# EEZ_DIB_DCM220_r2B7.net
KiCad netlist of a schematic drawn in EAGLE
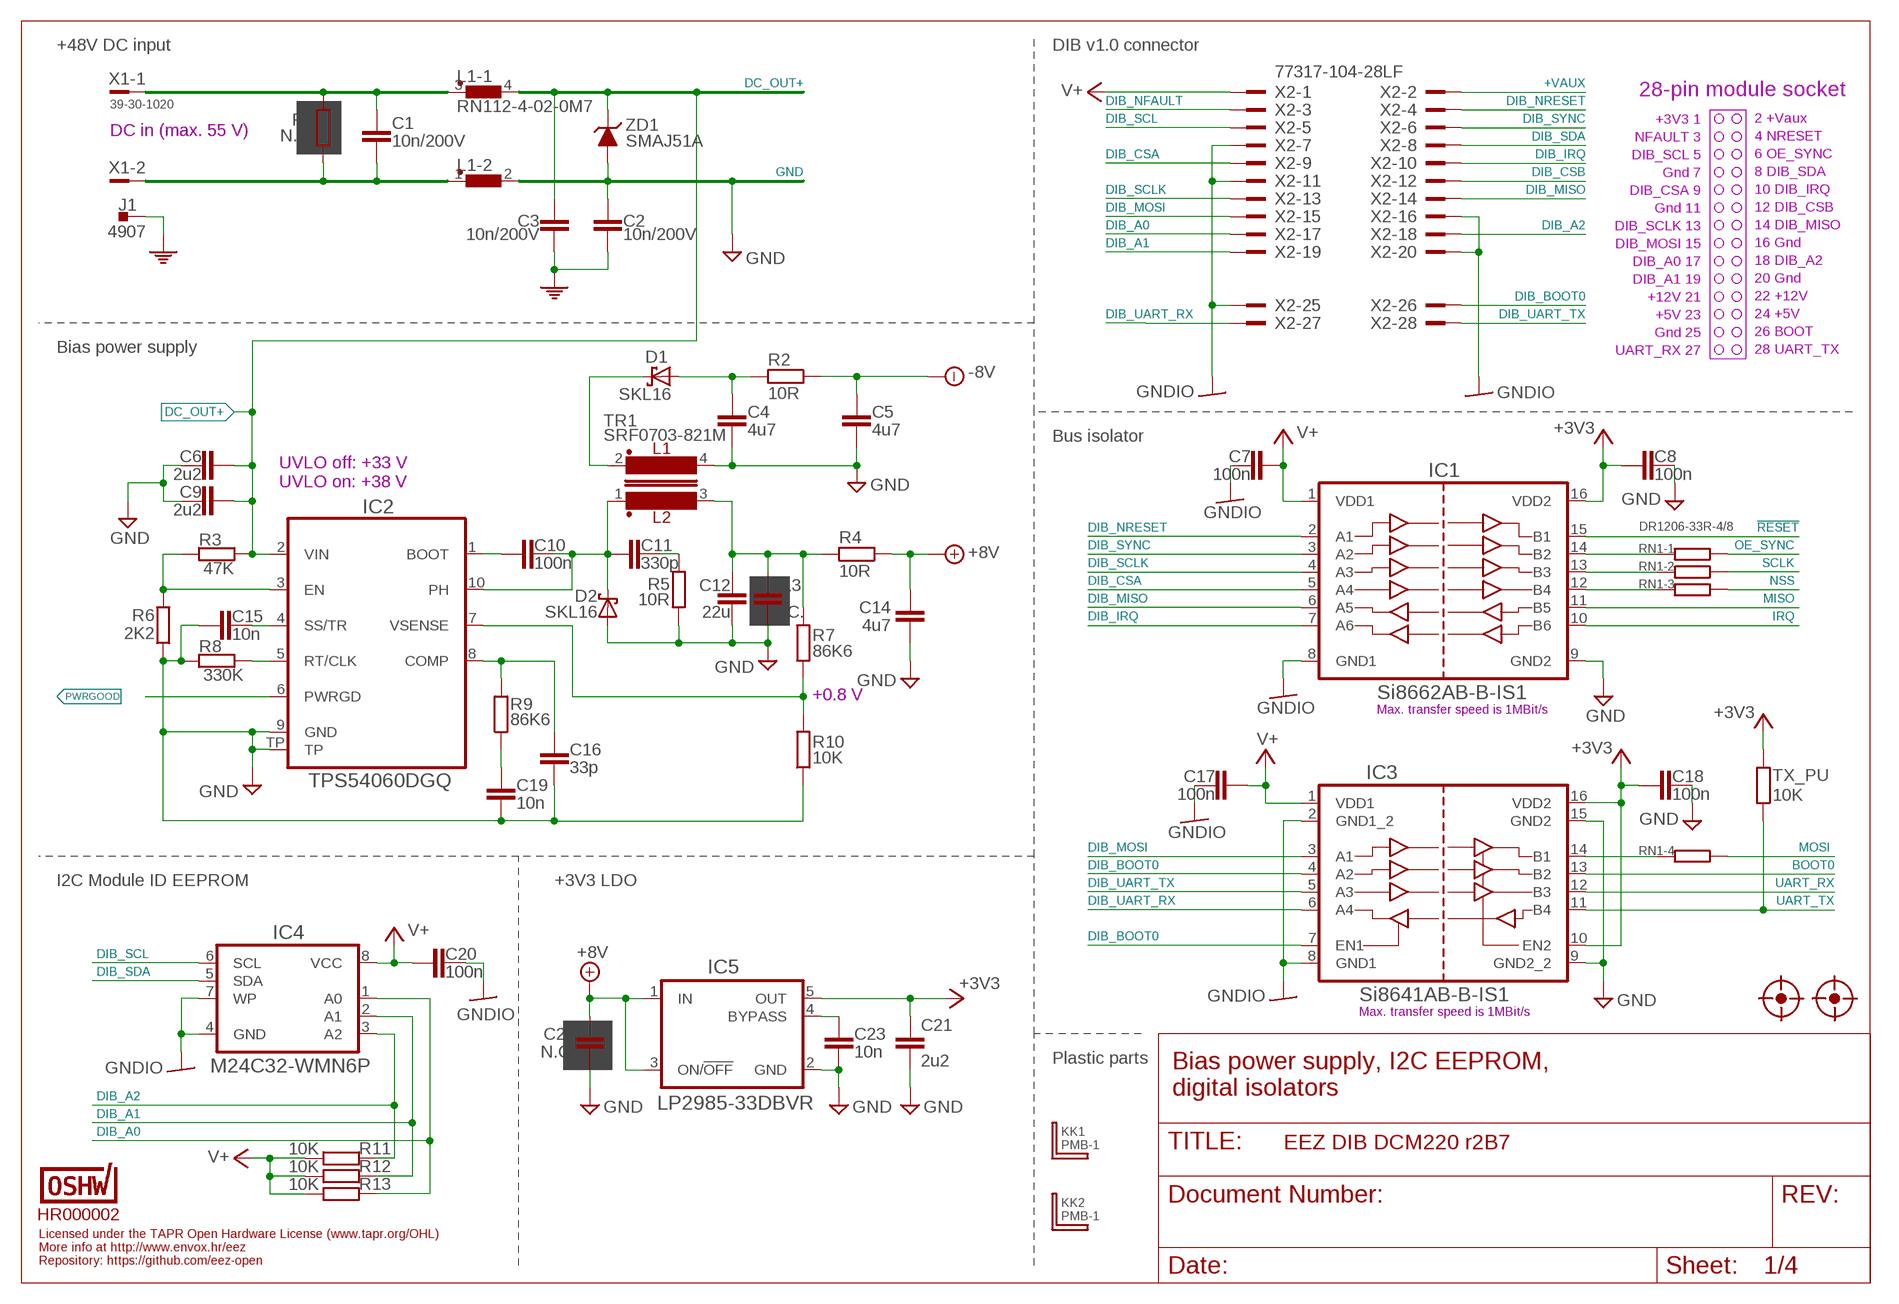
[diagram p0: schematic, sheet 1]
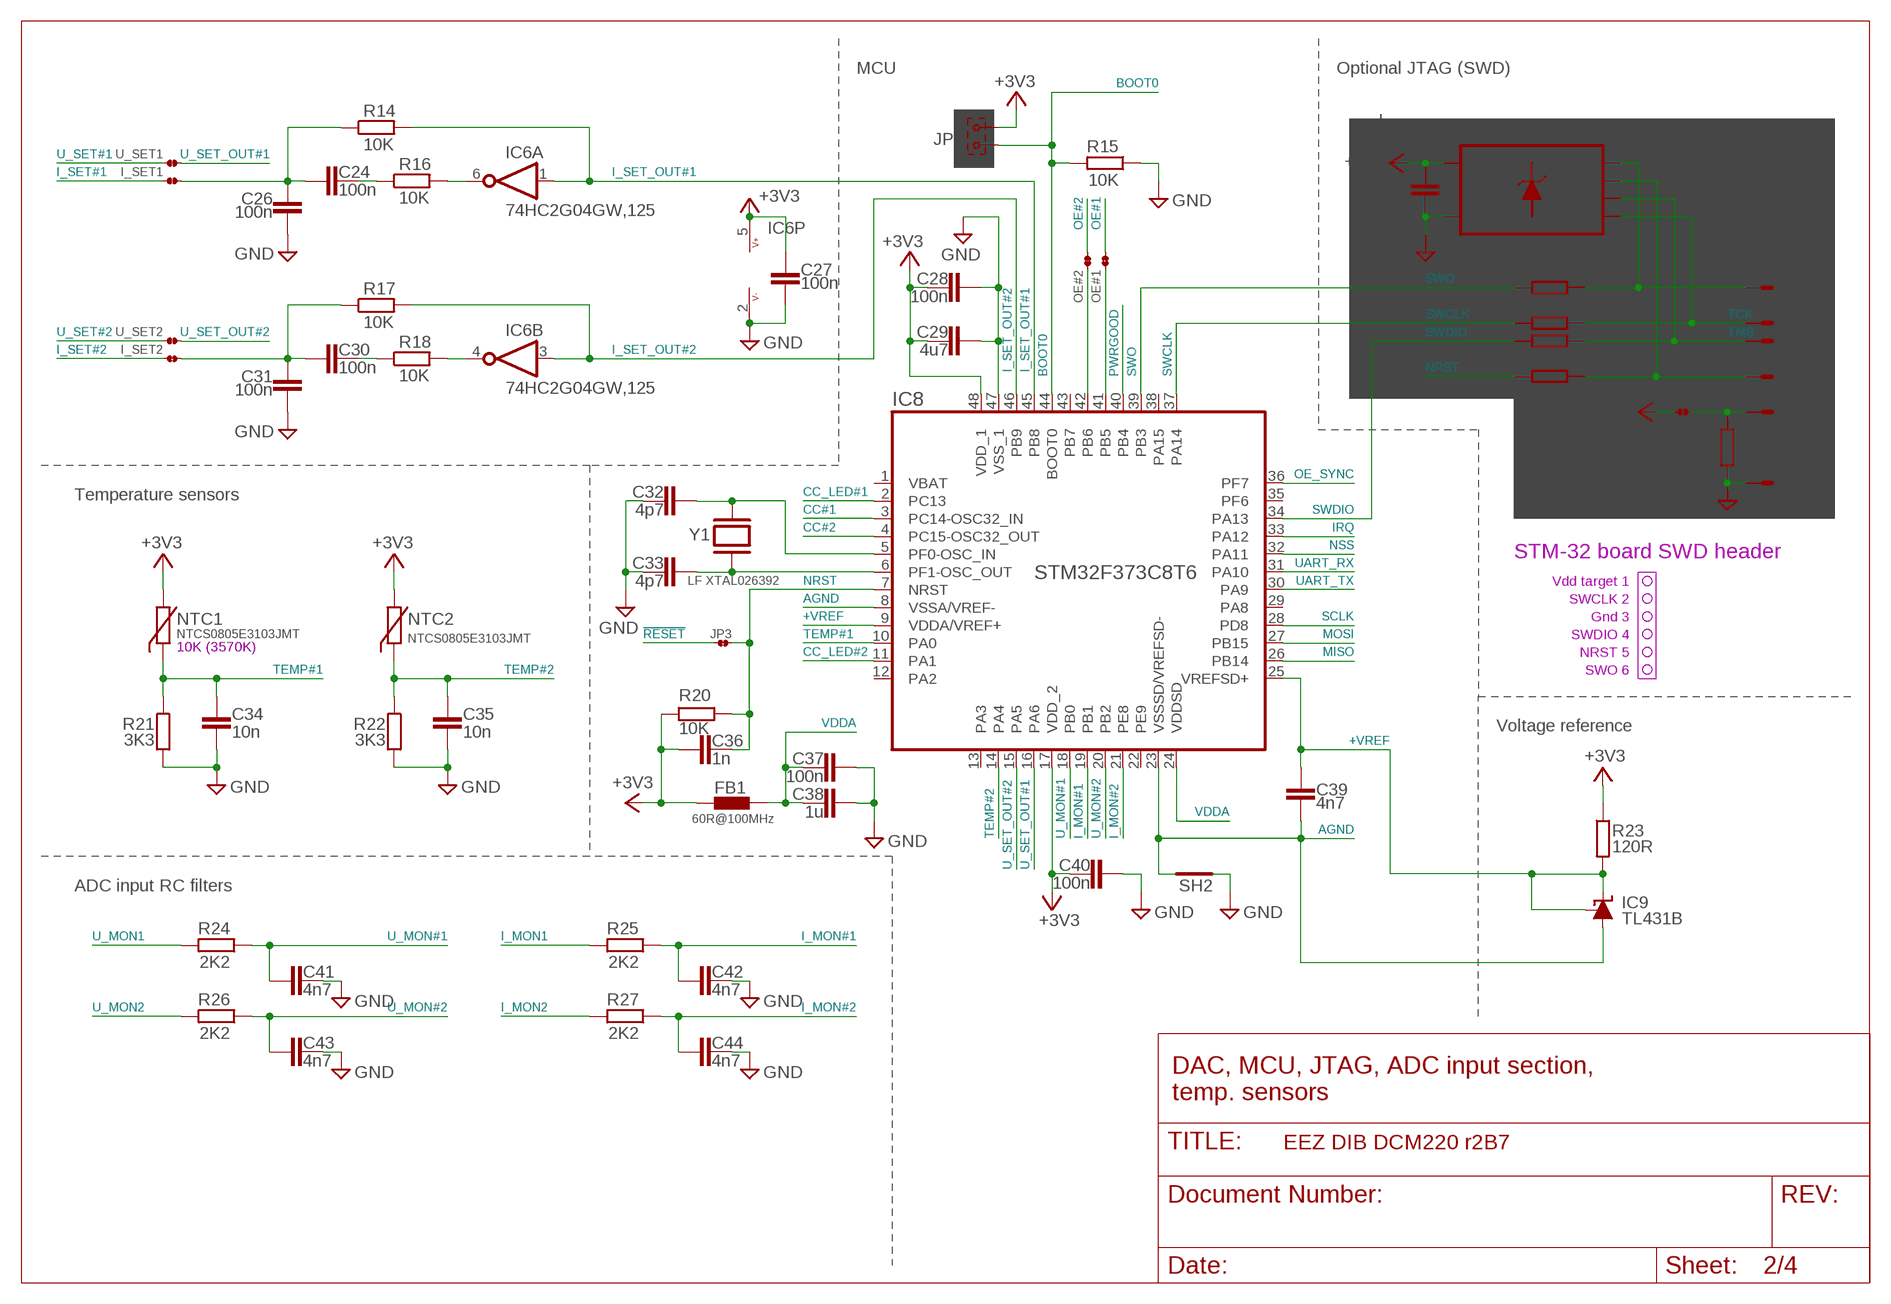
[diagram p1: schematic, sheet 2]
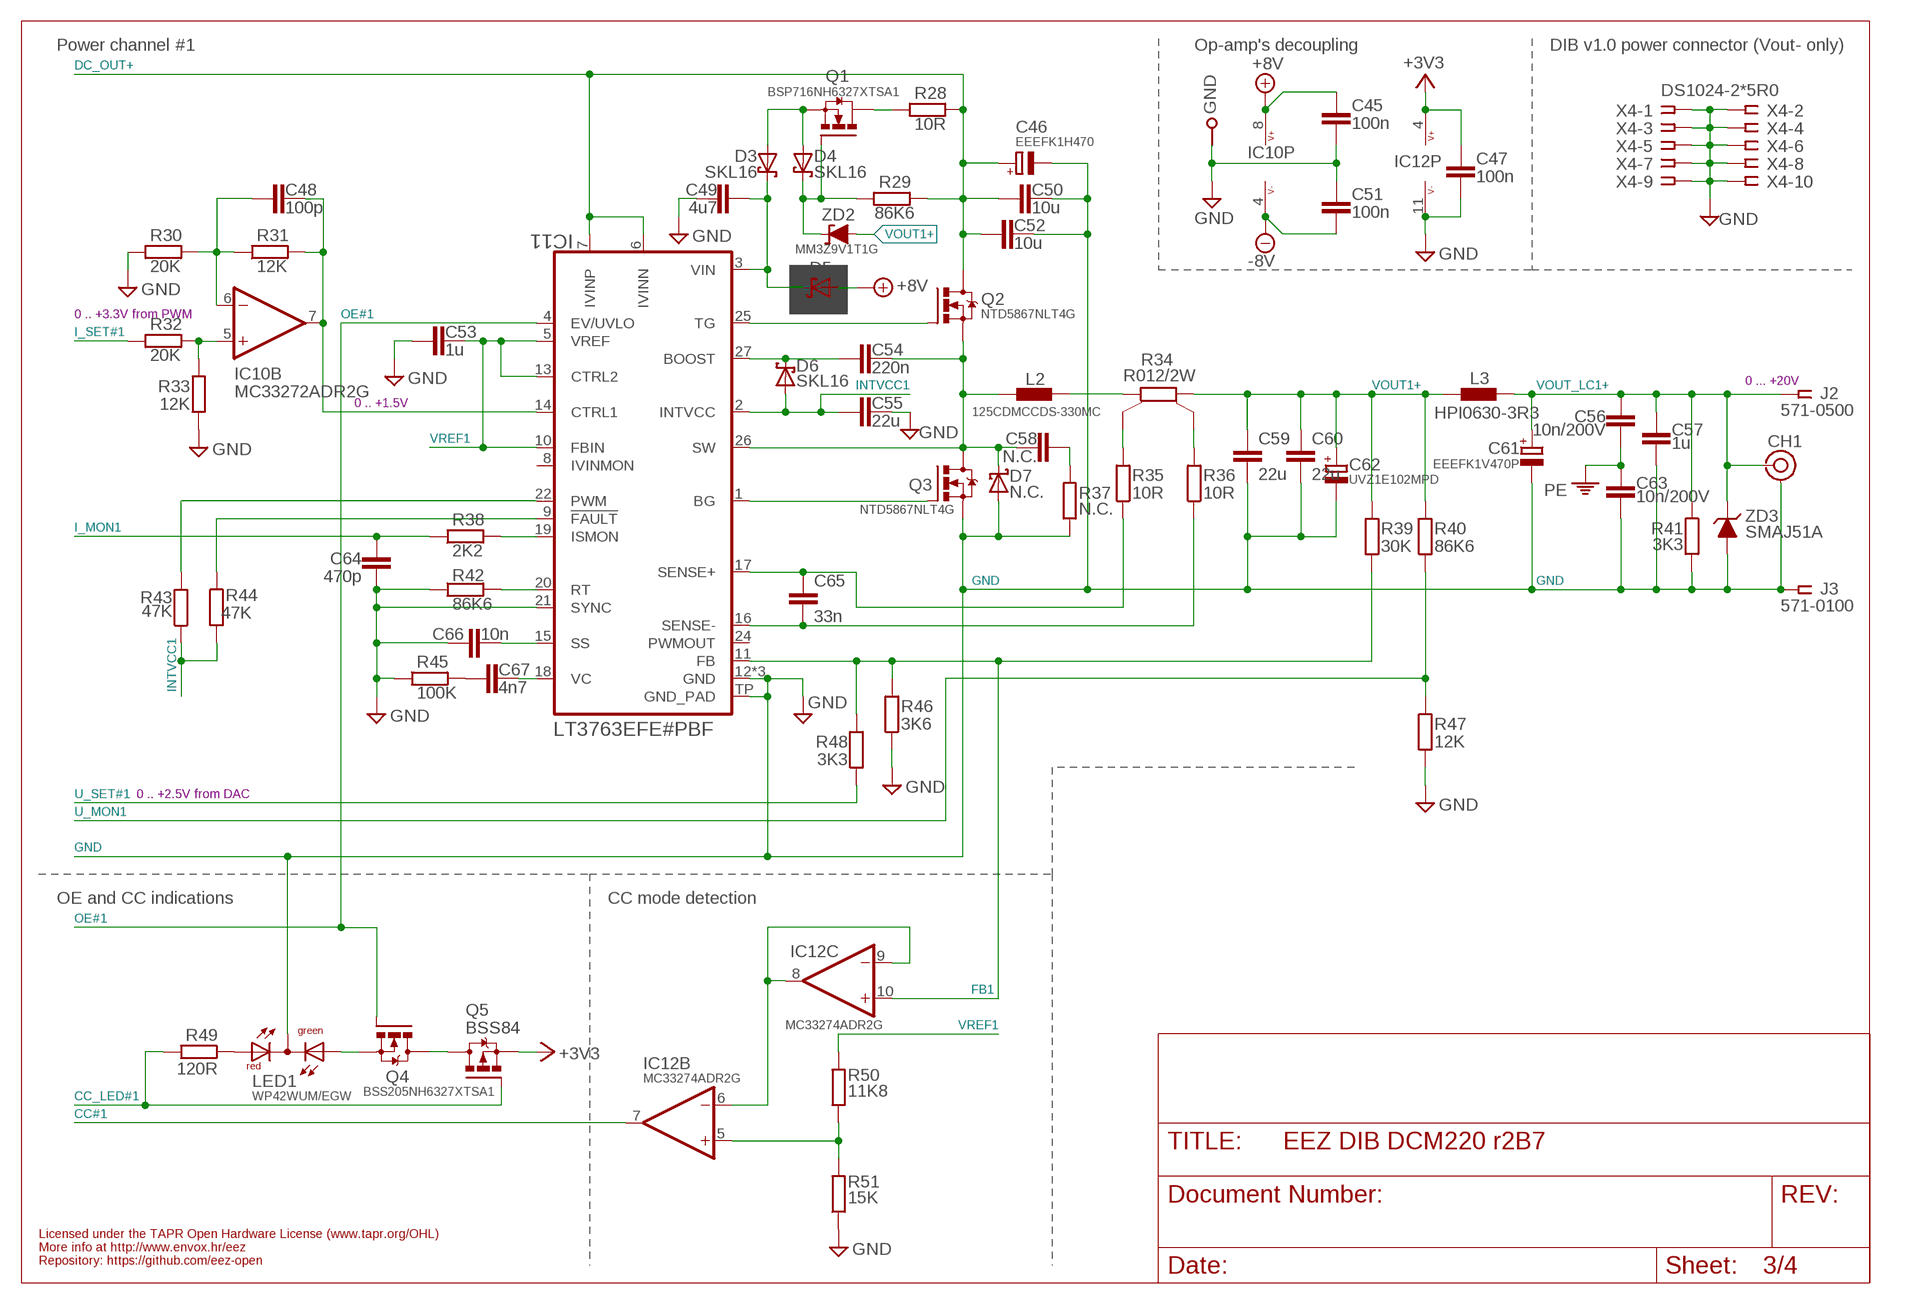
[diagram p2: schematic, sheet 3]
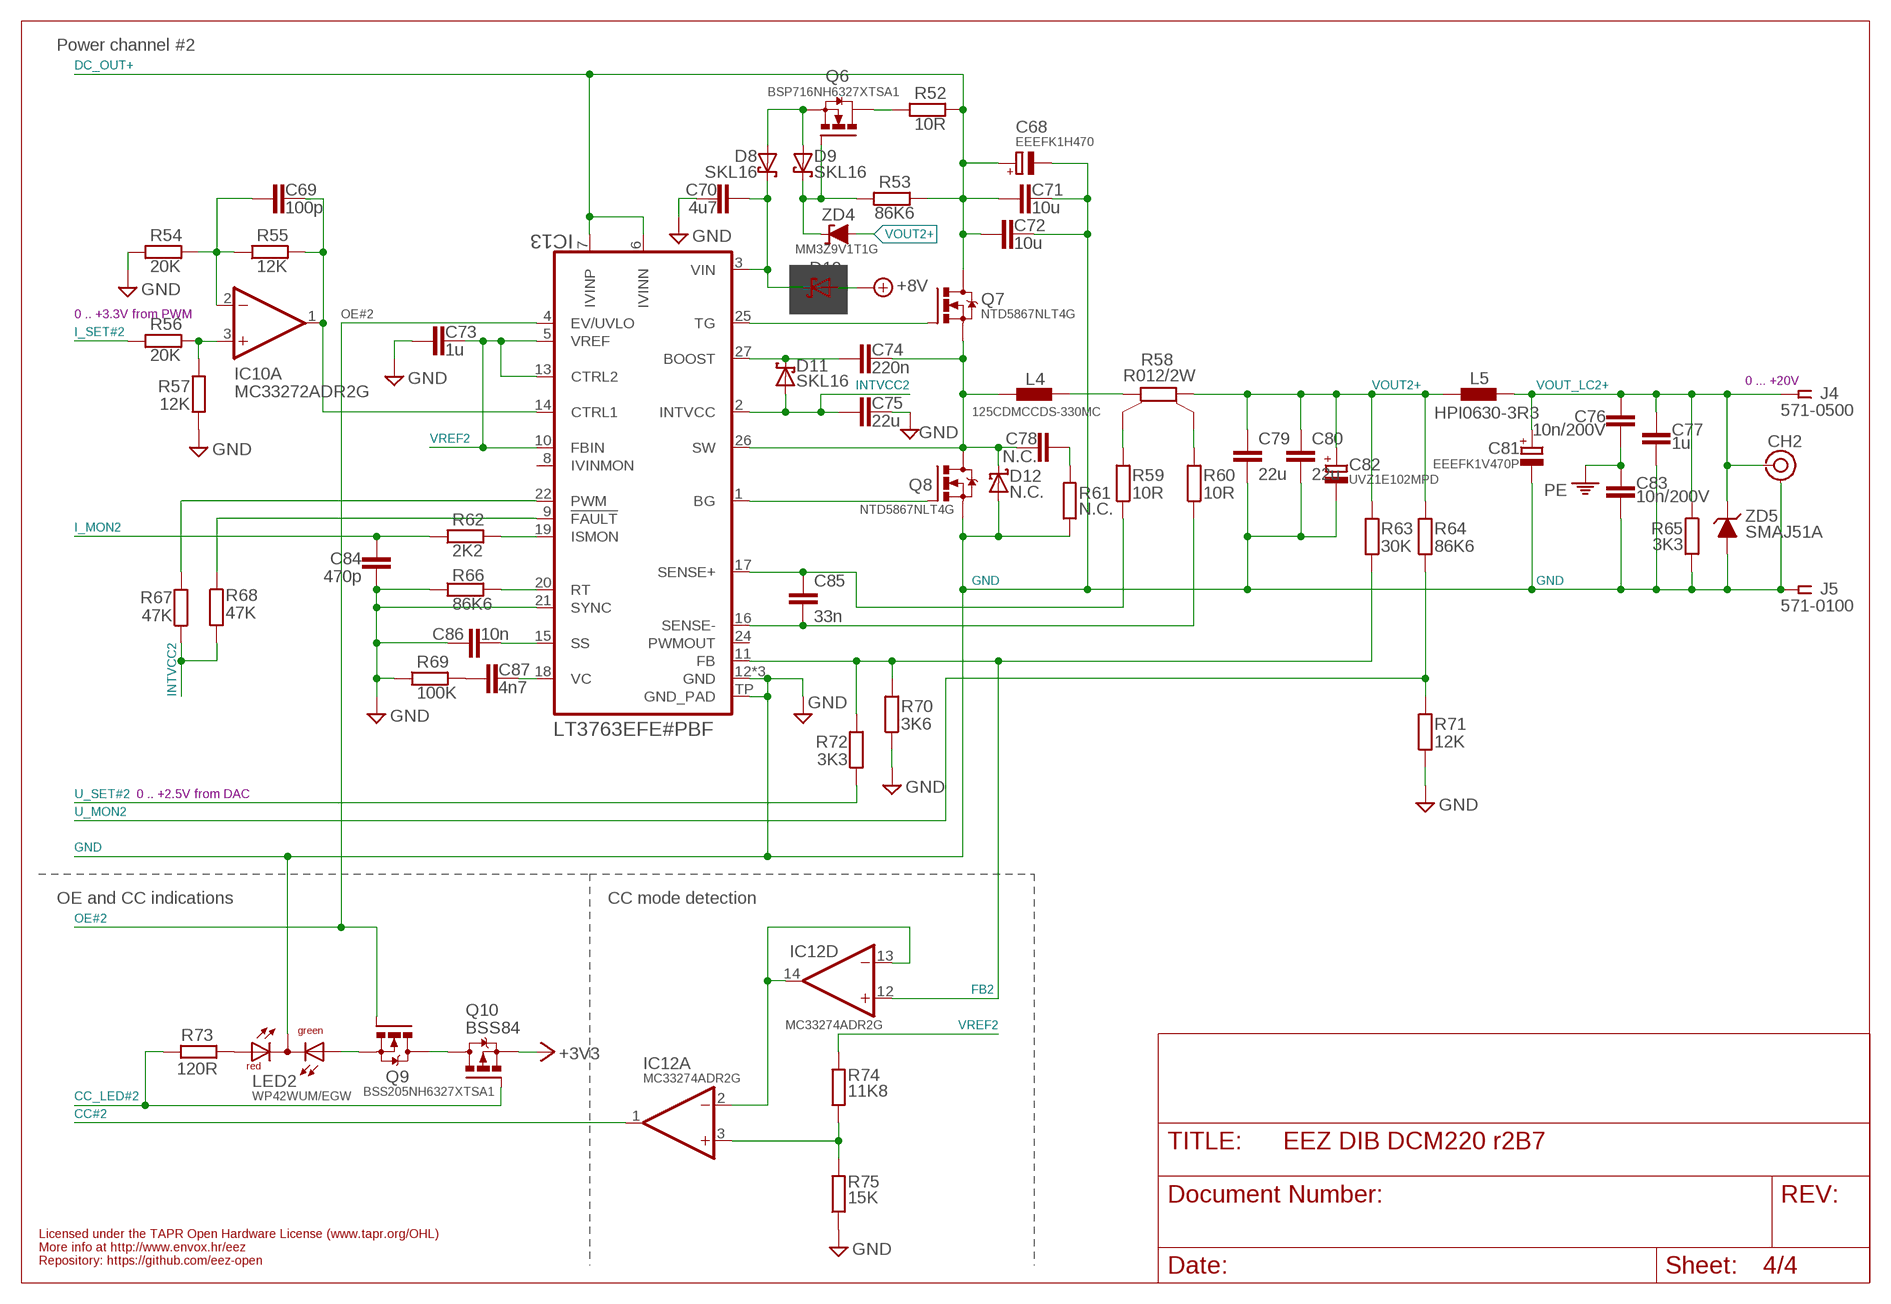
[diagram p3: schematic, sheet 4]

(export (version "E")
  (design (tool "Eeschema 10.0.6"))
  (components
    (comp (ref "C68")
      (value "EEEFK1H470")
      (footprint "eagle-import:CAPAE830X1050N")
      (libsource (lib "eagle-import") (part "ECAPSMD8.3MM/HA0"))
    )
    (comp (ref "C69")
      (value "100p")
      (footprint "eagle-import:C0805")
      (libsource (lib "eagle-import") (part "C-EUC0805"))
    )
    (comp (ref "C70")
      (value "4u7")
      (footprint "eagle-import:C1206")
      (libsource (lib "eagle-import") (part "C-EUC1206"))
    )
    (comp (ref "C71")
      (value "10u")
      (footprint "eagle-import:C1210")
      (libsource (lib "eagle-import") (part "C-EUC1210"))
    )
    (comp (ref "C72")
      (value "10u")
      (footprint "eagle-import:C1210")
      (libsource (lib "eagle-import") (part "C-EUC1210"))
    )
    (comp (ref "C73")
      (value "1u")
      (footprint "eagle-import:C0805")
      (libsource (lib "eagle-import") (part "C-EUC0805"))
    )
    (comp (ref "C74")
      (value "220n")
      (footprint "eagle-import:C0805")
      (libsource (lib "eagle-import") (part "C-EUC0805"))
    )
    (comp (ref "C75")
      (value "22u")
      (footprint "eagle-import:C1206")
      (libsource (lib "eagle-import") (part "C-EUC1206"))
    )
    (comp (ref "C76")
      (value "10n/200V")
      (footprint "eagle-import:C1206")
      (libsource (lib "eagle-import") (part "C-EUC1206"))
    )
    (comp (ref "C77")
      (value "1u")
      (footprint "eagle-import:C0805")
      (libsource (lib "eagle-import") (part "C-EUC0805"))
    )
    (comp (ref "C78")
      (value "N.C.")
      (footprint "eagle-import:C0805")
      (libsource (lib "eagle-import") (part "C-EUC0805"))
    )
    (comp (ref "C79")
      (value "22u")
      (footprint "eagle-import:C1210")
      (libsource (lib "eagle-import") (part "C-EUC1210"))
    )
    (comp (ref "C80")
      (value "22u")
      (footprint "eagle-import:C1210")
      (libsource (lib "eagle-import") (part "C-EUC1210"))
    )
    (comp (ref "C81")
      (value "EEEFK1V470P")
      (footprint "eagle-import:CAPAE660X610N")
      (libsource (lib "eagle-import") (part "ECAPPANASONIC_H"))
    )
    (comp (ref "C82")
      (value "UVZ1E102MPD")
      (footprint "eagle-import:ECAP5_10.5")
      (libsource (lib "eagle-import") (part "ECAP5G_10.5MM"))
    )
    (comp (ref "C83")
      (value "10n/200V")
      (footprint "eagle-import:C1206")
      (libsource (lib "eagle-import") (part "C-EUC1206"))
    )
    (comp (ref "C84")
      (value "470p")
      (footprint "eagle-import:C0805")
      (libsource (lib "eagle-import") (part "C-EUC0805"))
    )
    (comp (ref "C85")
      (value "33n")
      (footprint "eagle-import:C0805")
      (libsource (lib "eagle-import") (part "C-EUC0805"))
    )
    (comp (ref "C86")
      (value "10n")
      (footprint "eagle-import:C0805")
      (libsource (lib "eagle-import") (part "C-EUC0805"))
    )
    (comp (ref "C87")
      (value "4n7")
      (footprint "eagle-import:C0805")
      (libsource (lib "eagle-import") (part "C-EUC0805"))
    )
    (comp (ref "CH2")
      (value "TEST_POINT-2")
      (footprint "eagle-import:TP_1.1MM_2")
      (libsource (lib "eagle-import") (part "TEST_POINT-2"))
    )
    (comp (ref "D8")
      (value "SKL16")
      (footprint "eagle-import:SOD123")
      (libsource (lib "eagle-import") (part "SCHOTTKYSOD123"))
    )
    (comp (ref "D9")
      (value "SKL16")
      (footprint "eagle-import:SOD123")
      (libsource (lib "eagle-import") (part "SCHOTTKYSOD123"))
    )
    (comp (ref "D10")
      (value "N.C.")
      (footprint "eagle-import:SOD123")
      (libsource (lib "eagle-import") (part "SCHOTTKYSOD123"))
    )
    (comp (ref "D11")
      (value "SKL16")
      (footprint "eagle-import:SOD123")
      (libsource (lib "eagle-import") (part "SCHOTTKYSOD123"))
    )
    (comp (ref "D12")
      (value "N.C.")
      (footprint "eagle-import:SMA")
      (libsource (lib "eagle-import") (part "SCHOTTKYSMA_DO-214AC"))
    )
    (comp (ref "IC10")
      (value "MC33272ADR2G")
      (footprint "eagle-import:SOIC127P600X173-8N")
      (libsource (lib "eagle-import") (part "TL072SOIC8"))
    )
    (comp (ref "IC12")
      (value "MC33274ADR2G")
      (footprint "eagle-import:SOIC127P600X175-14N")
      (fields (field (name "MPN") "TL074ACD"))
      (libsource (lib "eagle-import") (part "TL074SOIC14"))
    )
    (comp (ref "IC13")
      (value "LT3763EFE#PBF")
      (footprint "eagle-import:LTC_05-08-1663-EB")
      (libsource (lib "eagle-import") (part "LT3763EFE#PBF"))
    )
    (comp (ref "J4")
      (value "571-0500")
      (footprint "eagle-import:DELTRON_571")
      (libsource (lib "eagle-import") (part "571-0500"))
    )
    (comp (ref "J5")
      (value "571-0100")
      (footprint "eagle-import:DELTRON_571")
      (libsource (lib "eagle-import") (part "571-0100"))
    )
    (comp (ref "L4")
      (value "125CDMCCDS-330MC")
      (footprint "eagle-import:125CDMCC_DS")
      (libsource (lib "eagle-import") (part "125CDMCC/DS"))
    )
    (comp (ref "L5")
      (value "HPI0630-3R3")
      (footprint "eagle-import:COILCRAFT_HPI0630")
      (libsource (lib "eagle-import") (part "COILCRAFT_HPI0630"))
    )
    (comp (ref "LED2")
      (value "WP42WUM/EGW")
      (footprint "eagle-import:L-42WUM-1EGWT")
      (libsource (lib "eagle-import") (part "LED_L-42WUM/1EGWT"))
    )
    (comp (ref "Q6")
      (value "BSP716NH6327XTSA1")
      (footprint "eagle-import:SOT223")
      (libsource (lib "eagle-import") (part "N-HEXFET-2D_?-SOT232IRLL014N"))
    )
    (comp (ref "Q7")
      (value "NTD5867NLT4G")
      (footprint "eagle-import:TO229P990X239-3N")
      (libsource (lib "eagle-import") (part "N-MOSFETDPAK"))
    )
    (comp (ref "Q8")
      (value "NTD5867NLT4G")
      (footprint "eagle-import:TO229P990X239-3N")
      (libsource (lib "eagle-import") (part "N-MOSFETDPAK"))
    )
    (comp (ref "Q9")
      (value "BSS205NH6327XTSA1")
      (footprint "eagle-import:SOT103P240X110-3N")
      (fields (field (name "MPN") "2N7002-7-F"))
      (libsource (lib "eagle-import") (part "2N7002"))
    )
    (comp (ref "Q10")
      (value "BSS84")
      (footprint "eagle-import:SOT95P237X112-3N")
      (fields (field (name "MPN") "IRLML2246TRPBF"))
      (libsource (lib "eagle-import") (part "IRLML2246TRPBF"))
    )
    (comp (ref "R52")
      (value "10R")
      (footprint "eagle-import:R0805")
      (libsource (lib "eagle-import") (part "R-EU_R0805"))
    )
    (comp (ref "R53")
      (value "86K6")
      (footprint "eagle-import:R0805")
      (libsource (lib "eagle-import") (part "R-EU_R0805"))
    )
    (comp (ref "R54")
      (value "20K")
      (footprint "eagle-import:R0805")
      (libsource (lib "eagle-import") (part "R-EU_R0805"))
    )
    (comp (ref "R55")
      (value "12K")
      (footprint "eagle-import:R0805")
      (libsource (lib "eagle-import") (part "R-EU_R0805"))
    )
    (comp (ref "R56")
      (value "20K")
      (footprint "eagle-import:R0805")
      (libsource (lib "eagle-import") (part "R-EU_R0805"))
    )
    (comp (ref "R57")
      (value "12K")
      (footprint "eagle-import:R0805")
      (libsource (lib "eagle-import") (part "R-EU_R0805"))
    )
    (comp (ref "R58")
      (value "R012/2W")
      (footprint "eagle-import:R_2512-4WIRE")
      (libsource (lib "eagle-import") (part "R-EU_4WIRE2512"))
    )
    (comp (ref "R59")
      (value "10R")
      (footprint "eagle-import:R0805")
      (libsource (lib "eagle-import") (part "R-EU_R0805"))
    )
    (comp (ref "R60")
      (value "10R")
      (footprint "eagle-import:R0805")
      (libsource (lib "eagle-import") (part "R-EU_R0805"))
    )
    (comp (ref "R61")
      (value "N.C.")
      (footprint "eagle-import:R1206")
      (libsource (lib "eagle-import") (part "R-EU_R1206"))
    )
    (comp (ref "R62")
      (value "2K2")
      (footprint "eagle-import:R0805")
      (libsource (lib "eagle-import") (part "R-EU_R0805"))
    )
    (comp (ref "R63")
      (value "30K")
      (footprint "eagle-import:R0805")
      (libsource (lib "eagle-import") (part "R-EU_R0805"))
    )
    (comp (ref "R64")
      (value "86K6")
      (footprint "eagle-import:R0805")
      (libsource (lib "eagle-import") (part "R-EU_R0805"))
    )
    (comp (ref "R65")
      (value "3K3")
      (footprint "eagle-import:R0805")
      (libsource (lib "eagle-import") (part "R-EU_R0805"))
    )
    (comp (ref "R66")
      (value "86K6")
      (footprint "eagle-import:R0805")
      (libsource (lib "eagle-import") (part "R-EU_R0805"))
    )
    (comp (ref "R67")
      (value "47K")
      (footprint "eagle-import:R0805")
      (libsource (lib "eagle-import") (part "R-EU_R0805"))
    )
    (comp (ref "R68")
      (value "47K")
      (footprint "eagle-import:R0805")
      (libsource (lib "eagle-import") (part "R-EU_R0805"))
    )
    (comp (ref "R69")
      (value "100K")
      (footprint "eagle-import:R0805")
      (libsource (lib "eagle-import") (part "R-EU_R0805"))
    )
    (comp (ref "R70")
      (value "3K6")
      (footprint "eagle-import:R0805")
      (libsource (lib "eagle-import") (part "R-EU_R0805"))
    )
    (comp (ref "R71")
      (value "12K")
      (footprint "eagle-import:R0805")
      (libsource (lib "eagle-import") (part "R-EU_R0805"))
    )
    (comp (ref "R72")
      (value "3K3")
      (footprint "eagle-import:R0805")
      (libsource (lib "eagle-import") (part "R-EU_R0805"))
    )
    (comp (ref "R73")
      (value "120R")
      (footprint "eagle-import:R0805")
      (libsource (lib "eagle-import") (part "R-EU_R0805"))
    )
    (comp (ref "R74")
      (value "11K8")
      (footprint "eagle-import:R0805")
      (libsource (lib "eagle-import") (part "R-EU_R0805"))
    )
    (comp (ref "R75")
      (value "15K")
      (footprint "eagle-import:R0805")
      (libsource (lib "eagle-import") (part "R-EU_R0805"))
    )
    (comp (ref "ZD4")
      (value "MM3Z9V1T1G")
      (footprint "eagle-import:SOD323-W")
      (libsource (lib "eagle-import") (part "ZENER-DIODESOD323"))
    )
    (comp (ref "ZD5")
      (value "SMAJ51A")
      (footprint "eagle-import:DO214AA")
      (libsource (lib "eagle-import") (part "P6SMB68A"))
    )
    (comp (ref "C45")
      (value "100n")
      (footprint "eagle-import:C0603")
      (libsource (lib "eagle-import") (part "C-EUC0603"))
    )
    (comp (ref "C46")
      (value "EEEFK1H470")
      (footprint "eagle-import:CAPAE830X1050N")
      (libsource (lib "eagle-import") (part "ECAPSMD8.3MM/HA0"))
    )
    (comp (ref "C47")
      (value "100n")
      (footprint "eagle-import:C0603")
      (libsource (lib "eagle-import") (part "C-EUC0603"))
    )
    (comp (ref "C48")
      (value "100p")
      (footprint "eagle-import:C0805")
      (libsource (lib "eagle-import") (part "C-EUC0805"))
    )
    (comp (ref "C49")
      (value "4u7")
      (footprint "eagle-import:C1206")
      (libsource (lib "eagle-import") (part "C-EUC1206"))
    )
    (comp (ref "C50")
      (value "10u")
      (footprint "eagle-import:C1210")
      (libsource (lib "eagle-import") (part "C-EUC1210"))
    )
    (comp (ref "C51")
      (value "100n")
      (footprint "eagle-import:C0603")
      (libsource (lib "eagle-import") (part "C-EUC0603"))
    )
    (comp (ref "C52")
      (value "10u")
      (footprint "eagle-import:C1210")
      (libsource (lib "eagle-import") (part "C-EUC1210"))
    )
    (comp (ref "C53")
      (value "1u")
      (footprint "eagle-import:C0805")
      (libsource (lib "eagle-import") (part "C-EUC0805"))
    )
    (comp (ref "C54")
      (value "220n")
      (footprint "eagle-import:C0805")
      (libsource (lib "eagle-import") (part "C-EUC0805"))
    )
    (comp (ref "C55")
      (value "22u")
      (footprint "eagle-import:C1206")
      (libsource (lib "eagle-import") (part "C-EUC1206"))
    )
    (comp (ref "C56")
      (value "10n/200V")
      (footprint "eagle-import:C1206")
      (libsource (lib "eagle-import") (part "C-EUC1206"))
    )
    (comp (ref "C57")
      (value "1u")
      (footprint "eagle-import:C0805")
      (libsource (lib "eagle-import") (part "C-EUC0805"))
    )
    (comp (ref "C58")
      (value "N.C.")
      (footprint "eagle-import:C0805")
      (libsource (lib "eagle-import") (part "C-EUC0805"))
    )
    (comp (ref "C59")
      (value "22u")
      (footprint "eagle-import:C1210")
      (libsource (lib "eagle-import") (part "C-EUC1210"))
    )
    (comp (ref "C60")
      (value "22u")
      (footprint "eagle-import:C1210")
      (libsource (lib "eagle-import") (part "C-EUC1210"))
    )
    (comp (ref "C61")
      (value "EEEFK1V470P")
      (footprint "eagle-import:CAPAE660X610N")
      (libsource (lib "eagle-import") (part "ECAPPANASONIC_H"))
    )
    (comp (ref "C62")
      (value "UVZ1E102MPD")
      (footprint "eagle-import:ECAP5_10.5")
      (libsource (lib "eagle-import") (part "ECAP5G_10.5MM"))
    )
    (comp (ref "C63")
      (value "10n/200V")
      (footprint "eagle-import:C1206")
      (libsource (lib "eagle-import") (part "C-EUC1206"))
    )
    (comp (ref "C64")
      (value "470p")
      (footprint "eagle-import:C0805")
      (libsource (lib "eagle-import") (part "C-EUC0805"))
    )
    (comp (ref "C65")
      (value "33n")
      (footprint "eagle-import:C0805")
      (libsource (lib "eagle-import") (part "C-EUC0805"))
    )
    (comp (ref "C66")
      (value "10n")
      (footprint "eagle-import:C0805")
      (libsource (lib "eagle-import") (part "C-EUC0805"))
    )
    (comp (ref "C67")
      (value "4n7")
      (footprint "eagle-import:C0805")
      (libsource (lib "eagle-import") (part "C-EUC0805"))
    )
    (comp (ref "CH1")
      (value "TEST_POINT-2")
      (footprint "eagle-import:TP_1.1MM_2")
      (libsource (lib "eagle-import") (part "TEST_POINT-2"))
    )
    (comp (ref "D3")
      (value "SKL16")
      (footprint "eagle-import:SOD123")
      (libsource (lib "eagle-import") (part "SCHOTTKYSOD123"))
    )
    (comp (ref "D4")
      (value "SKL16")
      (footprint "eagle-import:SOD123")
      (libsource (lib "eagle-import") (part "SCHOTTKYSOD123"))
    )
    (comp (ref "D5")
      (value "N.C.")
      (footprint "eagle-import:SOD123")
      (libsource (lib "eagle-import") (part "SCHOTTKYSOD123"))
    )
    (comp (ref "D6")
      (value "SKL16")
      (footprint "eagle-import:SOD123")
      (libsource (lib "eagle-import") (part "SCHOTTKYSOD123"))
    )
    (comp (ref "D7")
      (value "N.C.")
      (footprint "eagle-import:SMA")
      (libsource (lib "eagle-import") (part "SCHOTTKYSMA_DO-214AC"))
    )
    (comp (ref "GND")
      (value "TEST-PIN_0.9MM")
      (footprint "eagle-import:TEST-PIN_0.9MM")
      (libsource (lib "eagle-import") (part "TEST-PIN_0.9MM"))
    )
    (comp (ref "IC11")
      (value "LT3763EFE#PBF")
      (footprint "eagle-import:LTC_05-08-1663-EB")
      (libsource (lib "eagle-import") (part "LT3763EFE#PBF"))
    )
    (comp (ref "J2")
      (value "571-0500")
      (footprint "eagle-import:DELTRON_571")
      (libsource (lib "eagle-import") (part "571-0500"))
    )
    (comp (ref "J3")
      (value "571-0100")
      (footprint "eagle-import:DELTRON_571")
      (libsource (lib "eagle-import") (part "571-0100"))
    )
    (comp (ref "L2")
      (value "125CDMCCDS-330MC")
      (footprint "eagle-import:125CDMCC_DS")
      (libsource (lib "eagle-import") (part "125CDMCC/DS"))
    )
    (comp (ref "L3")
      (value "HPI0630-3R3")
      (footprint "eagle-import:COILCRAFT_HPI0630")
      (libsource (lib "eagle-import") (part "COILCRAFT_HPI0630"))
    )
    (comp (ref "LED1")
      (value "WP42WUM/EGW")
      (footprint "eagle-import:L-42WUM-1EGWT")
      (libsource (lib "eagle-import") (part "LED_L-42WUM/1EGWT"))
    )
    (comp (ref "Q1")
      (value "BSP716NH6327XTSA1")
      (footprint "eagle-import:SOT223")
      (libsource (lib "eagle-import") (part "N-HEXFET-2D_?-SOT232IRLL014N"))
    )
    (comp (ref "Q2")
      (value "NTD5867NLT4G")
      (footprint "eagle-import:TO229P990X239-3N")
      (libsource (lib "eagle-import") (part "N-MOSFETDPAK"))
    )
    (comp (ref "Q3")
      (value "NTD5867NLT4G")
      (footprint "eagle-import:TO229P990X239-3N")
      (libsource (lib "eagle-import") (part "N-MOSFETDPAK"))
    )
    (comp (ref "Q4")
      (value "BSS205NH6327XTSA1")
      (footprint "eagle-import:SOT103P240X110-3N")
      (fields (field (name "MPN") "2N7002-7-F"))
      (libsource (lib "eagle-import") (part "2N7002"))
    )
    (comp (ref "Q5")
      (value "BSS84")
      (footprint "eagle-import:SOT95P237X112-3N")
      (fields (field (name "MPN") "IRLML2246TRPBF"))
      (libsource (lib "eagle-import") (part "IRLML2246TRPBF"))
    )
    (comp (ref "R28")
      (value "10R")
      (footprint "eagle-import:R0805")
      (libsource (lib "eagle-import") (part "R-EU_R0805"))
    )
    (comp (ref "R29")
      (value "86K6")
      (footprint "eagle-import:R0805")
      (libsource (lib "eagle-import") (part "R-EU_R0805"))
    )
    (comp (ref "R30")
      (value "20K")
      (footprint "eagle-import:R0805")
      (libsource (lib "eagle-import") (part "R-EU_R0805"))
    )
    (comp (ref "R31")
      (value "12K")
      (footprint "eagle-import:R0805")
      (libsource (lib "eagle-import") (part "R-EU_R0805"))
    )
    (comp (ref "R32")
      (value "20K")
      (footprint "eagle-import:R0805")
      (libsource (lib "eagle-import") (part "R-EU_R0805"))
    )
    (comp (ref "R33")
      (value "12K")
      (footprint "eagle-import:R0805")
      (libsource (lib "eagle-import") (part "R-EU_R0805"))
    )
    (comp (ref "R34")
      (value "R012/2W")
      (footprint "eagle-import:R_2512-4WIRE")
      (libsource (lib "eagle-import") (part "R-EU_4WIRE2512"))
    )
    (comp (ref "R35")
      (value "10R")
      (footprint "eagle-import:R0805")
      (libsource (lib "eagle-import") (part "R-EU_R0805"))
    )
    (comp (ref "R36")
      (value "10R")
      (footprint "eagle-import:R0805")
      (libsource (lib "eagle-import") (part "R-EU_R0805"))
    )
    (comp (ref "R37")
      (value "N.C.")
      (footprint "eagle-import:R1206")
      (libsource (lib "eagle-import") (part "R-EU_R1206"))
    )
    (comp (ref "R38")
      (value "2K2")
      (footprint "eagle-import:R0805")
      (libsource (lib "eagle-import") (part "R-EU_R0805"))
    )
    (comp (ref "R39")
      (value "30K")
      (footprint "eagle-import:R0805")
      (libsource (lib "eagle-import") (part "R-EU_R0805"))
    )
    (comp (ref "R40")
      (value "86K6")
      (footprint "eagle-import:R0805")
      (libsource (lib "eagle-import") (part "R-EU_R0805"))
    )
    (comp (ref "R41")
      (value "3K3")
      (footprint "eagle-import:R0805")
      (libsource (lib "eagle-import") (part "R-EU_R0805"))
    )
    (comp (ref "R42")
      (value "86K6")
      (footprint "eagle-import:R0805")
      (libsource (lib "eagle-import") (part "R-EU_R0805"))
    )
    (comp (ref "R43")
      (value "47K")
      (footprint "eagle-import:R0805")
      (libsource (lib "eagle-import") (part "R-EU_R0805"))
    )
    (comp (ref "R44")
      (value "47K")
      (footprint "eagle-import:R0805")
      (libsource (lib "eagle-import") (part "R-EU_R0805"))
    )
    (comp (ref "R45")
      (value "100K")
      (footprint "eagle-import:R0805")
      (libsource (lib "eagle-import") (part "R-EU_R0805"))
    )
    (comp (ref "R46")
      (value "3K6")
      (footprint "eagle-import:R0805")
      (libsource (lib "eagle-import") (part "R-EU_R0805"))
    )
    (comp (ref "R47")
      (value "12K")
      (footprint "eagle-import:R0805")
      (libsource (lib "eagle-import") (part "R-EU_R0805"))
    )
    (comp (ref "R48")
      (value "3K3")
      (footprint "eagle-import:R0805")
      (libsource (lib "eagle-import") (part "R-EU_R0805"))
    )
    (comp (ref "R49")
      (value "120R")
      (footprint "eagle-import:R0805")
      (libsource (lib "eagle-import") (part "R-EU_R0805"))
    )
    (comp (ref "R50")
      (value "11K8")
      (footprint "eagle-import:R0805")
      (libsource (lib "eagle-import") (part "R-EU_R0805"))
    )
    (comp (ref "R51")
      (value "15K")
      (footprint "eagle-import:R0805")
      (libsource (lib "eagle-import") (part "R-EU_R0805"))
    )
    (comp (ref "X4")
      (value "DS1024-2*5R0")
      (footprint "eagle-import:SSW-105-02-T-D-RA")
      (libsource (lib "eagle-import") (part "SSW-105-02-T-D-RA"))
    )
    (comp (ref "ZD2")
      (value "MM3Z9V1T1G")
      (footprint "eagle-import:SOD323-W")
      (libsource (lib "eagle-import") (part "ZENER-DIODESOD323"))
    )
    (comp (ref "ZD3")
      (value "SMAJ51A")
      (footprint "eagle-import:DO214AA")
      (libsource (lib "eagle-import") (part "P6SMB68A"))
    )
    (comp (ref "C24")
      (value "100n")
      (footprint "eagle-import:C0603")
      (libsource (lib "eagle-import") (part "C-EUC0603"))
    )
    (comp (ref "C25")
      (value "N.C.")
      (footprint "eagle-import:C0603")
      (libsource (lib "eagle-import") (part "C-EUC0603"))
    )
    (comp (ref "C26")
      (value "100n")
      (footprint "eagle-import:C0603")
      (libsource (lib "eagle-import") (part "C-EUC0603"))
    )
    (comp (ref "C27")
      (value "100n")
      (footprint "eagle-import:C0603")
      (libsource (lib "eagle-import") (part "C-EUC0603"))
    )
    (comp (ref "C28")
      (value "100n")
      (footprint "eagle-import:C0603")
      (libsource (lib "eagle-import") (part "C-EUC0603"))
    )
    (comp (ref "C29")
      (value "4u7")
      (footprint "eagle-import:C1206")
      (libsource (lib "eagle-import") (part "C-EUC1206"))
    )
    (comp (ref "C30")
      (value "100n")
      (footprint "eagle-import:C0603")
      (libsource (lib "eagle-import") (part "C-EUC0603"))
    )
    (comp (ref "C31")
      (value "100n")
      (footprint "eagle-import:C0603")
      (libsource (lib "eagle-import") (part "C-EUC0603"))
    )
    (comp (ref "C32")
      (value "4p7")
      (footprint "eagle-import:C0603")
      (libsource (lib "eagle-import") (part "C-EUC0603"))
    )
    (comp (ref "C33")
      (value "4p7")
      (footprint "eagle-import:C0603")
      (libsource (lib "eagle-import") (part "C-EUC0603"))
    )
    (comp (ref "C34")
      (value "10n")
      (footprint "eagle-import:C0805")
      (libsource (lib "eagle-import") (part "C-EUC0805"))
    )
    (comp (ref "C35")
      (value "10n")
      (footprint "eagle-import:C0805")
      (libsource (lib "eagle-import") (part "C-EUC0805"))
    )
    (comp (ref "C36")
      (value "1n")
      (footprint "eagle-import:C0805")
      (libsource (lib "eagle-import") (part "C-EUC0805"))
    )
    (comp (ref "C37")
      (value "100n")
      (footprint "eagle-import:C0603")
      (libsource (lib "eagle-import") (part "C-EUC0603"))
    )
    (comp (ref "C38")
      (value "1u")
      (footprint "eagle-import:C0805")
      (libsource (lib "eagle-import") (part "C-EUC0805"))
    )
    (comp (ref "C39")
      (value "4n7")
      (footprint "eagle-import:C0805")
      (libsource (lib "eagle-import") (part "C-EUC0805"))
    )
    (comp (ref "C40")
      (value "100n")
      (footprint "eagle-import:C0603")
      (libsource (lib "eagle-import") (part "C-EUC0603"))
    )
    (comp (ref "C41")
      (value "4n7")
      (footprint "eagle-import:C0805")
      (libsource (lib "eagle-import") (part "C-EUC0805"))
    )
    (comp (ref "C42")
      (value "4n7")
      (footprint "eagle-import:C0805")
      (libsource (lib "eagle-import") (part "C-EUC0805"))
    )
    (comp (ref "C43")
      (value "4n7")
      (footprint "eagle-import:C0805")
      (libsource (lib "eagle-import") (part "C-EUC0805"))
    )
    (comp (ref "C44")
      (value "4n7")
      (footprint "eagle-import:C0805")
      (libsource (lib "eagle-import") (part "C-EUC0805"))
    )
    (comp (ref "FB1")
      (value "60R@100MHz")
      (footprint "eagle-import:BEAD0603")
      (libsource (lib "eagle-import") (part "FERRITE_BEAD0603"))
    )
    (comp (ref "IC6")
      (value "74HC2G04GW,125")
      (footprint "eagle-import:SOT65P210X110-6N")
      (libsource (lib "eagle-import") (part "74HC2G04"))
    )
    (comp (ref "IC7")
      (value "N.C.")
      (footprint "eagle-import:DRL6")
      (libsource (lib "eagle-import") (part "TPD4E001-DRL"))
    )
    (comp (ref "IC8")
      (value "STM32F373C8T6")
      (footprint "eagle-import:LQFP-48")
      (libsource (lib "eagle-import") (part "STM32F373C8T6"))
    )
    (comp (ref "IC9")
      (value "TL431B")
      (footprint "eagle-import:SOT103P240X110-3N")
      (libsource (lib "eagle-import") (part "TL431"))
    )
    (comp (ref "I_SET1")
      (value "JP2-NOCUT")
      (footprint "eagle-import:JP2-NOCUT")
      (libsource (lib "eagle-import") (part "JP2-NOCUT"))
    )
    (comp (ref "I_SET2")
      (value "JP2-NOCUT")
      (footprint "eagle-import:JP2-NOCUT")
      (libsource (lib "eagle-import") (part "JP2-NOCUT"))
    )
    (comp (ref "JP1")
      (value "JUMPER-2PIN-2MM")
      (footprint "eagle-import:2MM-2")
      (libsource (lib "eagle-import") (part "JUMPER-2PIN-2MM"))
    )
    (comp (ref "JP2")
      (value "JP2-CUT")
      (footprint "eagle-import:JP2-CUT")
      (libsource (lib "eagle-import") (part "JP2-CUT"))
    )
    (comp (ref "JP3")
      (value "JP2-NOCUT")
      (footprint "eagle-import:JP2-NOCUT")
      (libsource (lib "eagle-import") (part "JP2-NOCUT"))
    )
    (comp (ref "NTC1")
      (value "NTCS0805E3103JMT")
      (footprint "eagle-import:R_0805")
      (libsource (lib "eagle-import") (part "NTCR_0805"))
    )
    (comp (ref "NTC2")
      (value "NTCS0805E3103JMT")
      (footprint "eagle-import:R_0805")
      (libsource (lib "eagle-import") (part "NTCR_0805"))
    )
    (comp (ref "OE#1")
      (value "JP2-NOCUT")
      (footprint "eagle-import:JP2-NOCUT")
      (libsource (lib "eagle-import") (part "JP2-NOCUT"))
    )
    (comp (ref "OE#2")
      (value "JP2-NOCUT")
      (footprint "eagle-import:JP2-NOCUT")
      (libsource (lib "eagle-import") (part "JP2-NOCUT"))
    )
    (comp (ref "R14")
      (value "10K")
      (footprint "eagle-import:R0805")
      (libsource (lib "eagle-import") (part "R-EU_R0805"))
    )
    (comp (ref "R15")
      (value "10K")
      (footprint "eagle-import:R0805")
      (libsource (lib "eagle-import") (part "R-EU_R0805"))
    )
    (comp (ref "R16")
      (value "10K")
      (footprint "eagle-import:R0805")
      (libsource (lib "eagle-import") (part "R-EU_R0805"))
    )
    (comp (ref "R17")
      (value "10K")
      (footprint "eagle-import:R0805")
      (libsource (lib "eagle-import") (part "R-EU_R0805"))
    )
    (comp (ref "R18")
      (value "10K")
      (footprint "eagle-import:R0805")
      (libsource (lib "eagle-import") (part "R-EU_R0805"))
    )
    (comp (ref "R19")
      (value "N.C.")
      (footprint "eagle-import:R0805")
      (libsource (lib "eagle-import") (part "R-EU_R0805"))
    )
    (comp (ref "R20")
      (value "10K")
      (footprint "eagle-import:R0805")
      (libsource (lib "eagle-import") (part "R-EU_R0805"))
    )
    (comp (ref "R21")
      (value "3K3")
      (footprint "eagle-import:R0805")
      (libsource (lib "eagle-import") (part "R-EU_R0805"))
    )
    (comp (ref "R22")
      (value "3K3")
      (footprint "eagle-import:R0805")
      (libsource (lib "eagle-import") (part "R-EU_R0805"))
    )
    (comp (ref "R23")
      (value "120R")
      (footprint "eagle-import:R0805")
      (libsource (lib "eagle-import") (part "R-EU_R0805"))
    )
    (comp (ref "R24")
      (value "2K2")
      (footprint "eagle-import:R0805")
      (libsource (lib "eagle-import") (part "R-EU_R0805"))
    )
    (comp (ref "R25")
      (value "2K2")
      (footprint "eagle-import:R0805")
      (libsource (lib "eagle-import") (part "R-EU_R0805"))
    )
    (comp (ref "R26")
      (value "2K2")
      (footprint "eagle-import:R0805")
      (libsource (lib "eagle-import") (part "R-EU_R0805"))
    )
    (comp (ref "R27")
      (value "2K2")
      (footprint "eagle-import:R0805")
      (libsource (lib "eagle-import") (part "R-EU_R0805"))
    )
    (comp (ref "RN2")
      (value "N.C.")
      (footprint "eagle-import:CAY16")
      (libsource (lib "eagle-import") (part "R_ARRAY4"))
    )
    (comp (ref "SH2")
      (value "SHORTNOHOLE")
      (footprint "eagle-import:SHORT_NOHOLE")
      (libsource (lib "eagle-import") (part "SHORTNOHOLE"))
    )
    (comp (ref "U_SET1")
      (value "JP2-NOCUT")
      (footprint "eagle-import:JP2-NOCUT")
      (libsource (lib "eagle-import") (part "JP2-NOCUT"))
    )
    (comp (ref "U_SET2")
      (value "JP2-NOCUT")
      (footprint "eagle-import:JP2-NOCUT")
      (libsource (lib "eagle-import") (part "JP2-NOCUT"))
    )
    (comp (ref "X3")
      (value "N.C.")
      (footprint "eagle-import:22-23-2061")
      (fields (field (name "MF") "MOLEX") (field (name "MPN") "22-23-2061"))
      (libsource (lib "eagle-import") (part "22-23-2061"))
    )
    (comp (ref "Y1")
      (value "LF XTAL026392")
      (footprint "eagle-import:12SMX(B)")
      (libsource (lib "eagle-import") (part "XTAL7.5X5.1-B"))
    )
    (comp (ref "C1")
      (value "10n/200V")
      (footprint "eagle-import:C1206")
      (libsource (lib "eagle-import") (part "C-EUC1206"))
    )
    (comp (ref "C2")
      (value "10n/200V")
      (footprint "eagle-import:C1206")
      (libsource (lib "eagle-import") (part "C-EUC1206"))
    )
    (comp (ref "C3")
      (value "10n/200V")
      (footprint "eagle-import:C1206")
      (libsource (lib "eagle-import") (part "C-EUC1206"))
    )
    (comp (ref "C4")
      (value "4u7")
      (footprint "eagle-import:C1206")
      (libsource (lib "eagle-import") (part "C-EUC1206"))
    )
    (comp (ref "C5")
      (value "4u7")
      (footprint "eagle-import:C1206")
      (libsource (lib "eagle-import") (part "C-EUC1206"))
    )
    (comp (ref "C6")
      (value "2u2")
      (footprint "eagle-import:C1206")
      (libsource (lib "eagle-import") (part "C-EUC1206"))
    )
    (comp (ref "C7")
      (value "100n")
      (footprint "eagle-import:C0603")
      (libsource (lib "eagle-import") (part "C-EUC0603"))
    )
    (comp (ref "C8")
      (value "100n")
      (footprint "eagle-import:C0603")
      (libsource (lib "eagle-import") (part "C-EUC0603"))
    )
    (comp (ref "C9")
      (value "2u2")
      (footprint "eagle-import:C1206")
      (libsource (lib "eagle-import") (part "C-EUC1206"))
    )
    (comp (ref "C10")
      (value "100n")
      (footprint "eagle-import:C0603")
      (libsource (lib "eagle-import") (part "C-EUC0603"))
    )
    (comp (ref "C11")
      (value "330p")
      (footprint "eagle-import:C0805")
      (libsource (lib "eagle-import") (part "C-EUC0805"))
    )
    (comp (ref "C12")
      (value "22u")
      (footprint "eagle-import:C1206")
      (libsource (lib "eagle-import") (part "C-EUC1206"))
    )
    (comp (ref "C13")
      (value "N.C.")
      (footprint "eagle-import:C1206")
      (libsource (lib "eagle-import") (part "C-EUC1206"))
    )
    (comp (ref "C14")
      (value "4u7")
      (footprint "eagle-import:C1206")
      (libsource (lib "eagle-import") (part "C-EUC1206"))
    )
    (comp (ref "C15")
      (value "10n")
      (footprint "eagle-import:C0805")
      (libsource (lib "eagle-import") (part "C-EUC0805"))
    )
    (comp (ref "C16")
      (value "33p")
      (footprint "eagle-import:C0603")
      (libsource (lib "eagle-import") (part "C-EUC0603"))
    )
    (comp (ref "C17")
      (value "100n")
      (footprint "eagle-import:C0603")
      (libsource (lib "eagle-import") (part "C-EUC0603"))
    )
    (comp (ref "C18")
      (value "100n")
      (footprint "eagle-import:C0603")
      (libsource (lib "eagle-import") (part "C-EUC0603"))
    )
    (comp (ref "C19")
      (value "10n")
      (footprint "eagle-import:C0805")
      (libsource (lib "eagle-import") (part "C-EUC0805"))
    )
    (comp (ref "C20")
      (value "100n")
      (footprint "eagle-import:C0603")
      (libsource (lib "eagle-import") (part "C-EUC0603"))
    )
    (comp (ref "C21")
      (value "2u2")
      (footprint "eagle-import:C1206")
      (libsource (lib "eagle-import") (part "C-EUC1206"))
    )
    (comp (ref "C22")
      (value "N.C.")
      (footprint "eagle-import:C0805")
      (libsource (lib "eagle-import") (part "C-EUC0805"))
    )
    (comp (ref "C23")
      (value "10n")
      (footprint "eagle-import:C0805")
      (libsource (lib "eagle-import") (part "C-EUC0805"))
    )
    (comp (ref "D1")
      (value "SKL16")
      (footprint "eagle-import:SOD123")
      (libsource (lib "eagle-import") (part "SCHOTTKYSOD123"))
    )
    (comp (ref "D2")
      (value "SKL16")
      (footprint "eagle-import:SOD123")
      (libsource (lib "eagle-import") (part "SCHOTTKYSOD123"))
    )
    (comp (ref "FM1")
      (value "FIDUCIAL_2")
      (footprint "eagle-import:FIDUCIAL_DUAL")
      (libsource (lib "eagle-import") (part "FIDUCIAL_2"))
    )
    (comp (ref "FM2")
      (value "FIDUCIAL_2")
      (footprint "eagle-import:FIDUCIAL_DUAL")
      (libsource (lib "eagle-import") (part "FIDUCIAL_2"))
    )
    (comp (ref "IC1")
      (value "Si8662AB-B-IS1")
      (footprint "eagle-import:SOIC-16")
      (libsource (lib "eagle-import") (part "SI8662NSOIC-16"))
    )
    (comp (ref "IC2")
      (value "TPS54060DGQ")
      (footprint "eagle-import:SOP50P490X110-11N")
      (fields (field (name "MPN") "TPS54060ADGQ"))
      (libsource (lib "eagle-import") (part "TPS54060DGQ"))
    )
    (comp (ref "IC3")
      (value "Si8641AB-B-IS1")
      (footprint "eagle-import:SOIC-16")
      (libsource (lib "eagle-import") (part "SI8641NSOIC-16"))
    )
    (comp (ref "IC4")
      (value "M24C32-WMN6P")
      (footprint "eagle-import:SOIC127P600X173-8N")
      (libsource (lib "eagle-import") (part "AT24CXXSOIC8"))
    )
    (comp (ref "IC5")
      (value "LP2985-33DBVR")
      (footprint "eagle-import:SOT95P270X145-5N")
      (libsource (lib "eagle-import") (part "LP2985"))
    )
    (comp (ref "J1")
      (value "4907")
      (footprint "eagle-import:PCB_TAB-4907")
      (libsource (lib "eagle-import") (part "PCB_TAB-4907"))
    )
    (comp (ref "KK1")
      (value "PMB-1")
      (footprint "eagle-import:PCB-MB")
      (libsource (lib "eagle-import") (part "PCB-MB"))
    )
    (comp (ref "KK2")
      (value "PMB-1")
      (footprint "eagle-import:PCB-MB")
      (libsource (lib "eagle-import") (part "PCB-MB"))
    )
    (comp (ref "L1")
      (value "RN112-4-02-0M7")
      (footprint "eagle-import:RN112")
      (libsource (lib "eagle-import") (part "RN112"))
    )
    (comp (ref "R1")
      (value "N.C.")
      (footprint "eagle-import:R2512")
      (libsource (lib "eagle-import") (part "R-EU_R2512"))
    )
    (comp (ref "R2")
      (value "10R")
      (footprint "eagle-import:R0805")
      (libsource (lib "eagle-import") (part "R-EU_R0805"))
    )
    (comp (ref "R3")
      (value "47K")
      (footprint "eagle-import:R0805")
      (libsource (lib "eagle-import") (part "R-EU_R0805"))
    )
    (comp (ref "R4")
      (value "10R")
      (footprint "eagle-import:R0805")
      (libsource (lib "eagle-import") (part "R-EU_R0805"))
    )
    (comp (ref "R5")
      (value "10R")
      (footprint "eagle-import:R0805")
      (libsource (lib "eagle-import") (part "R-EU_R0805"))
    )
    (comp (ref "R6")
      (value "2K2")
      (footprint "eagle-import:R0805")
      (libsource (lib "eagle-import") (part "R-EU_R0805"))
    )
    (comp (ref "R7")
      (value "86K6")
      (footprint "eagle-import:R0805")
      (libsource (lib "eagle-import") (part "R-EU_R0805"))
    )
    (comp (ref "R8")
      (value "330K")
      (footprint "eagle-import:R0805")
      (libsource (lib "eagle-import") (part "R-EU_R0805"))
    )
    (comp (ref "R9")
      (value "86K6")
      (footprint "eagle-import:R0805")
      (libsource (lib "eagle-import") (part "R-EU_R0805"))
    )
    (comp (ref "R10")
      (value "10K")
      (footprint "eagle-import:R0805")
      (libsource (lib "eagle-import") (part "R-EU_R0805"))
    )
    (comp (ref "R11")
      (value "10K")
      (footprint "eagle-import:R0805")
      (libsource (lib "eagle-import") (part "R-EU_R0805"))
    )
    (comp (ref "R12")
      (value "10K")
      (footprint "eagle-import:R0805")
      (libsource (lib "eagle-import") (part "R-EU_R0805"))
    )
    (comp (ref "R13")
      (value "10K")
      (footprint "eagle-import:R0805")
      (libsource (lib "eagle-import") (part "R-EU_R0805"))
    )
    (comp (ref "RN1")
      (value "DR1206-33R-4/8")
      (footprint "eagle-import:CAY16")
      (libsource (lib "eagle-import") (part "R_ARRAY4"))
    )
    (comp (ref "TR1")
      (value "SRF0703-821M")
      (footprint "eagle-import:SRF0703")
      (libsource (lib "eagle-import") (part "BOURNS_SRF0703INV"))
    )
    (comp (ref "TX_PU")
      (value "10K")
      (footprint "eagle-import:R0805")
      (libsource (lib "eagle-import") (part "R-EU_R0805"))
    )
    (comp (ref "U$3")
      (value "HR000002")
      (footprint "eagle-import:CERT-SMALL-SILK")
      (libsource (lib "eagle-import") (part "CERT-SMALL"))
    )
    (comp (ref "X1")
      (value "39-30-1020")
      (footprint "eagle-import:MINIFIT_39301020")
      (libsource (lib "eagle-import") (part "MINIFIT_39301020"))
    )
    (comp (ref "X2")
      (value "77317-104-28LF")
      (footprint "eagle-import:77317-104-28LF")
      (libsource (lib "eagle-import") (part "77317-104-28LF"))
    )
    (comp (ref "ZD1")
      (value "SMAJ51A")
      (footprint "eagle-import:DO214AA")
      (libsource (lib "eagle-import") (part "P6SMB68A"))
    )
  )
  (nets
    (net (code "1") (name "+3V3") (class "Default")
      (node (ref "C18") (pin "2") (pinfunction "2_2") (pintype "passive"))
      (node (ref "C21") (pin "1") (pinfunction "1_1") (pintype "passive"))
      (node (ref "C25") (pin "1") (pinfunction "1_1") (pintype "passive"))
      (node (ref "C27") (pin "1") (pinfunction "1_1") (pintype "passive"))
      (node (ref "C28") (pin "2") (pinfunction "2_2") (pintype "passive"))
      (node (ref "C29") (pin "1") (pinfunction "1_1") (pintype "passive"))
      (node (ref "C36") (pin "2") (pinfunction "2_2") (pintype "passive"))
      (node (ref "C40") (pin "2") (pinfunction "2_2") (pintype "passive"))
      (node (ref "C47") (pin "1") (pinfunction "1_1") (pintype "passive"))
      (node (ref "C8") (pin "2") (pinfunction "2_2") (pintype "passive"))
      (node (ref "FB1") (pin "P$1") (pinfunction "1_P$1") (pintype "passive"))
      (node (ref "IC1") (pin "16") (pinfunction "VDD2_16") (pintype "passive"))
      (node (ref "IC12") (pin "4") (pinfunction "V+_4") (pintype "power_in"))
      (node (ref "IC3") (pin "10") (pinfunction "EN2_10") (pintype "input"))
      (node (ref "IC3") (pin "16") (pinfunction "VDD2_16") (pintype "passive"))
      (node (ref "IC5") (pin "5") (pinfunction "OUT_5") (pintype "passive"))
      (node (ref "IC6") (pin "5") (pinfunction "V+_5") (pintype "power_in"))
      (node (ref "IC7") (pin "6") (pinfunction "VCC_6") (pintype "passive"))
      (node (ref "IC8") (pin "17") (pinfunction "VDD_2_17") (pintype "passive"))
      (node (ref "IC8") (pin "48") (pinfunction "VDD_1_48") (pintype "bidirectional"))
      (node (ref "JP1") (pin "1") (pinfunction "1_1") (pintype "passive"))
      (node (ref "JP2") (pin "1") (pinfunction "1_1") (pintype "passive"))
      (node (ref "NTC1") (pin "1") (pinfunction "P$1_1") (pintype "bidirectional"))
      (node (ref "NTC2") (pin "1") (pinfunction "P$1_1") (pintype "bidirectional"))
      (node (ref "Q10") (pin "2") (pinfunction "S_2") (pintype "passive"))
      (node (ref "Q5") (pin "2") (pinfunction "S_2") (pintype "passive"))
      (node (ref "R20") (pin "1") (pinfunction "1_1") (pintype "passive"))
      (node (ref "R23") (pin "1") (pinfunction "1_1") (pintype "passive"))
      (node (ref "TX_PU") (pin "2") (pinfunction "2_2") (pintype "passive"))
    )
    (net (code "2") (name "+8V") (class "Default")
      (node (ref "C14") (pin "1") (pinfunction "1_1") (pintype "passive"))
      (node (ref "C22") (pin "2") (pinfunction "2_2") (pintype "passive"))
      (node (ref "C45") (pin "1") (pinfunction "1_1") (pintype "passive"))
      (node (ref "D10") (pin "A") (pinfunction "A_A") (pintype "passive"))
      (node (ref "D5") (pin "A") (pinfunction "A_A") (pintype "passive"))
      (node (ref "IC10") (pin "8") (pinfunction "V+_8") (pintype "power_in"))
      (node (ref "IC5") (pin "1") (pinfunction "IN_1") (pintype "input"))
      (node (ref "IC5") (pin "3") (pinfunction "ON/~{OFF}_3") (pintype "input"))
      (node (ref "R4") (pin "1") (pinfunction "1_1") (pintype "passive"))
    )
    (net (code "3") (name "+VAUX") (class "Default")
      (node (ref "X2") (pin "2") (pinfunction "1_2") (pintype "passive"))
    )
    (net (code "4") (name "+VREF") (class "Default")
      (node (ref "C39") (pin "2") (pinfunction "2_2") (pintype "passive"))
      (node (ref "IC8") (pin "25") (pinfunction "VREFSD+_25") (pintype "passive"))
      (node (ref "IC8") (pin "9") (pinfunction "VDDA/VREF+_9") (pintype "passive"))
      (node (ref "IC9") (pin "1") (pinfunction "C_1") (pintype "passive"))
      (node (ref "IC9") (pin "2") (pinfunction "R_2") (pintype "passive"))
      (node (ref "R23") (pin "2") (pinfunction "2_2") (pintype "passive"))
    )
    (net (code "5") (name "-8V") (class "Default")
      (node (ref "C5") (pin "1") (pinfunction "1_1") (pintype "passive"))
      (node (ref "C51") (pin "2") (pinfunction "2_2") (pintype "passive"))
      (node (ref "IC10") (pin "4") (pinfunction "V-_4") (pintype "power_in"))
      (node (ref "R2") (pin "1") (pinfunction "1_1") (pintype "passive"))
    )
    (net (code "6") (name "AGND") (class "Default")
      (node (ref "C39") (pin "1") (pinfunction "1_1") (pintype "passive"))
      (node (ref "IC8") (pin "23") (pinfunction "VSSSD/VREFSD-_23") (pintype "passive"))
      (node (ref "IC8") (pin "8") (pinfunction "VSSA/VREF-_8") (pintype "passive"))
      (node (ref "IC9") (pin "3") (pinfunction "A_3") (pintype "passive"))
      (node (ref "SH2") (pin "1") (pinfunction "GND_A_1") (pintype "bidirectional"))
    )
    (net (code "7") (name "BOOT0") (class "Default")
      (node (ref "IC3") (pin "13") (pinfunction "B2_13") (pintype "output"))
      (node (ref "IC8") (pin "44") (pinfunction "BOOT0_44") (pintype "input"))
      (node (ref "JP1") (pin "2") (pinfunction "2_2") (pintype "passive"))
      (node (ref "R15") (pin "2") (pinfunction "2_2") (pintype "passive"))
    )
    (net (code "8") (name "CC#1") (class "Default")
      (node (ref "IC12") (pin "7") (pinfunction "OUT_7") (pintype "output"))
      (node (ref "IC8") (pin "3") (pinfunction "PC14-OSC32_IN_3") (pintype "bidirectional"))
    )
    (net (code "9") (name "CC#2") (class "Default")
      (node (ref "IC12") (pin "1") (pinfunction "OUT_1") (pintype "output"))
      (node (ref "IC8") (pin "4") (pinfunction "PC15-OSC32_OUT_4") (pintype "bidirectional"))
    )
    (net (code "10") (name "CC_LED#1") (class "Default")
      (node (ref "IC8") (pin "2") (pinfunction "PC13_2") (pintype "bidirectional"))
      (node (ref "Q5") (pin "1") (pinfunction "G_1") (pintype "passive"))
      (node (ref "R49") (pin "2") (pinfunction "2_2") (pintype "passive"))
    )
    (net (code "11") (name "CC_LED#2") (class "Default")
      (node (ref "IC8") (pin "11") (pinfunction "PA1_11") (pintype "bidirectional"))
      (node (ref "Q10") (pin "1") (pinfunction "G_1") (pintype "passive"))
      (node (ref "R73") (pin "2") (pinfunction "2_2") (pintype "passive"))
    )
    (net (code "12") (name "DC_OUT+") (class "Default")
      (node (ref "C3") (pin "2") (pinfunction "2_2") (pintype "passive"))
      (node (ref "C46") (pin "+") (pinfunction "+_+") (pintype "passive"))
      (node (ref "C50") (pin "1") (pinfunction "1_1") (pintype "passive"))
      (node (ref "C52") (pin "1") (pinfunction "1_1") (pintype "passive"))
      (node (ref "C6") (pin "1") (pinfunction "1_1") (pintype "passive"))
      (node (ref "C68") (pin "+") (pinfunction "+_+") (pintype "passive"))
      (node (ref "C71") (pin "1") (pinfunction "1_1") (pintype "passive"))
      (node (ref "C72") (pin "1") (pinfunction "1_1") (pintype "passive"))
      (node (ref "C9") (pin "1") (pinfunction "1_1") (pintype "passive"))
      (node (ref "IC11") (pin "6") (pinfunction "IVINN_6") (pintype "input"))
      (node (ref "IC11") (pin "7") (pinfunction "IVINP_7") (pintype "input"))
      (node (ref "IC13") (pin "6") (pinfunction "IVINN_6") (pintype "input"))
      (node (ref "IC13") (pin "7") (pinfunction "IVINP_7") (pintype "input"))
      (node (ref "IC2") (pin "2") (pinfunction "VIN_2") (pintype "power_in"))
      (node (ref "L1") (pin "4") (pinfunction "2_4") (pintype "passive"))
      (node (ref "Q2") (pin "2") (pinfunction "D_2") (pintype "passive"))
      (node (ref "Q7") (pin "2") (pinfunction "D_2") (pintype "passive"))
      (node (ref "R28") (pin "1") (pinfunction "1_1") (pintype "passive"))
      (node (ref "R29") (pin "1") (pinfunction "1_1") (pintype "passive"))
      (node (ref "R3") (pin "2") (pinfunction "2_2") (pintype "passive"))
      (node (ref "R52") (pin "1") (pinfunction "1_1") (pintype "passive"))
      (node (ref "R53") (pin "1") (pinfunction "1_1") (pintype "passive"))
      (node (ref "ZD1") (pin "C") (pinfunction "C_C") (pintype "passive"))
    )
    (net (code "13") (name "DIB_A0") (class "Default")
      (node (ref "IC4") (pin "1") (pinfunction "A0_1") (pintype "input"))
      (node (ref "R13") (pin "2") (pinfunction "2_2") (pintype "passive"))
      (node (ref "X2") (pin "17") (pinfunction "1_17") (pintype "passive"))
    )
    (net (code "14") (name "DIB_A1") (class "Default")
      (node (ref "IC4") (pin "2") (pinfunction "A1_2") (pintype "input"))
      (node (ref "R12") (pin "2") (pinfunction "2_2") (pintype "passive"))
      (node (ref "X2") (pin "19") (pinfunction "1_19") (pintype "passive"))
    )
    (net (code "15") (name "DIB_A2") (class "Default")
      (node (ref "IC4") (pin "3") (pinfunction "A2_3") (pintype "input"))
      (node (ref "R11") (pin "2") (pinfunction "2_2") (pintype "passive"))
      (node (ref "X2") (pin "18") (pinfunction "1_18") (pintype "passive"))
    )
    (net (code "16") (name "DIB_BOOT0") (class "Default")
      (node (ref "IC3") (pin "4") (pinfunction "A2_4") (pintype "input"))
      (node (ref "IC3") (pin "7") (pinfunction "EN1_7") (pintype "input"))
      (node (ref "X2") (pin "26") (pinfunction "1_26") (pintype "passive"))
    )
    (net (code "17") (name "DIB_CSA") (class "Default")
      (node (ref "IC1") (pin "5") (pinfunction "A4_5") (pintype "input"))
      (node (ref "X2") (pin "9") (pinfunction "1_9") (pintype "passive"))
    )
    (net (code "18") (name "DIB_CSB") (class "Default")
      (node (ref "X2") (pin "12") (pinfunction "1_12") (pintype "passive"))
    )
    (net (code "19") (name "DIB_IRQ") (class "Default")
      (node (ref "IC1") (pin "7") (pinfunction "A6_7") (pintype "output"))
      (node (ref "X2") (pin "10") (pinfunction "1_10") (pintype "passive"))
    )
    (net (code "20") (name "DIB_MISO") (class "Default")
      (node (ref "IC1") (pin "6") (pinfunction "A5_6") (pintype "output"))
      (node (ref "X2") (pin "14") (pinfunction "1_14") (pintype "passive"))
    )
    (net (code "21") (name "DIB_MOSI") (class "Default")
      (node (ref "IC3") (pin "3") (pinfunction "A1_3") (pintype "input"))
      (node (ref "X2") (pin "15") (pinfunction "1_15") (pintype "passive"))
    )
    (net (code "22") (name "DIB_NFAULT") (class "Default")
      (node (ref "X2") (pin "3") (pinfunction "1_3") (pintype "passive"))
    )
    (net (code "23") (name "DIB_NRESET") (class "Default")
      (node (ref "IC1") (pin "2") (pinfunction "A1_2") (pintype "input"))
      (node (ref "X2") (pin "4") (pinfunction "1_4") (pintype "passive"))
    )
    (net (code "24") (name "DIB_SCL") (class "Default")
      (node (ref "IC4") (pin "6") (pinfunction "SCL_6") (pintype "bidirectional"))
      (node (ref "X2") (pin "5") (pinfunction "1_5") (pintype "passive"))
    )
    (net (code "25") (name "DIB_SCLK") (class "Default")
      (node (ref "IC1") (pin "4") (pinfunction "A3_4") (pintype "input"))
      (node (ref "X2") (pin "13") (pinfunction "1_13") (pintype "passive"))
    )
    (net (code "26") (name "DIB_SDA") (class "Default")
      (node (ref "IC4") (pin "5") (pinfunction "SDA_5") (pintype "bidirectional"))
      (node (ref "X2") (pin "8") (pinfunction "1_8") (pintype "passive"))
    )
    (net (code "27") (name "DIB_SYNC") (class "Default")
      (node (ref "IC1") (pin "3") (pinfunction "A2_3") (pintype "input"))
      (node (ref "X2") (pin "6") (pinfunction "1_6") (pintype "passive"))
    )
    (net (code "28") (name "DIB_UART_RX") (class "Default")
      (node (ref "IC3") (pin "6") (pinfunction "A4_6") (pintype "output"))
      (node (ref "X2") (pin "27") (pinfunction "1_27") (pintype "passive"))
    )
    (net (code "29") (name "DIB_UART_TX") (class "Default")
      (node (ref "IC3") (pin "5") (pinfunction "A3_5") (pintype "input"))
      (node (ref "X2") (pin "28") (pinfunction "1_28") (pintype "passive"))
    )
    (net (code "30") (name "FB1") (class "Default")
      (node (ref "IC11") (pin "11") (pinfunction "FB_11") (pintype "input"))
      (node (ref "IC12") (pin "10") (pinfunction "+IN_10") (pintype "input"))
      (node (ref "R39") (pin "1") (pinfunction "1_1") (pintype "passive"))
      (node (ref "R46") (pin "2") (pinfunction "2_2") (pintype "passive"))
      (node (ref "R48") (pin "2") (pinfunction "2_2") (pintype "passive"))
    )
    (net (code "31") (name "FB2") (class "Default")
      (node (ref "IC12") (pin "12") (pinfunction "+IN_12") (pintype "input"))
      (node (ref "IC13") (pin "11") (pinfunction "FB_11") (pintype "input"))
      (node (ref "R63") (pin "1") (pinfunction "1_1") (pintype "passive"))
      (node (ref "R70") (pin "2") (pinfunction "2_2") (pintype "passive"))
      (node (ref "R72") (pin "2") (pinfunction "2_2") (pintype "passive"))
    )
    (net (code "32") (name "GND") (class "Default")
      (node (ref "C12") (pin "2") (pinfunction "2_2") (pintype "passive"))
      (node (ref "C13") (pin "2") (pinfunction "2_2") (pintype "passive"))
      (node (ref "C14") (pin "2") (pinfunction "2_2") (pintype "passive"))
      (node (ref "C15") (pin "2") (pinfunction "2_2") (pintype "passive"))
      (node (ref "C16") (pin "1") (pinfunction "1_1") (pintype "passive"))
      (node (ref "C18") (pin "1") (pinfunction "1_1") (pintype "passive"))
      (node (ref "C19") (pin "1") (pinfunction "1_1") (pintype "passive"))
      (node (ref "C2") (pin "1") (pinfunction "1_1") (pintype "passive"))
      (node (ref "C21") (pin "2") (pinfunction "2_2") (pintype "passive"))
      (node (ref "C22") (pin "1") (pinfunction "1_1") (pintype "passive"))
      (node (ref "C23") (pin "1") (pinfunction "1_1") (pintype "passive"))
      (node (ref "C25") (pin "2") (pinfunction "2_2") (pintype "passive"))
      (node (ref "C26") (pin "2") (pinfunction "2_2") (pintype "passive"))
      (node (ref "C27") (pin "2") (pinfunction "2_2") (pintype "passive"))
      (node (ref "C28") (pin "1") (pinfunction "1_1") (pintype "passive"))
      (node (ref "C29") (pin "2") (pinfunction "2_2") (pintype "passive"))
      (node (ref "C31") (pin "2") (pinfunction "2_2") (pintype "passive"))
      (node (ref "C32") (pin "1") (pinfunction "1_1") (pintype "passive"))
      (node (ref "C33") (pin "1") (pinfunction "1_1") (pintype "passive"))
      (node (ref "C34") (pin "1") (pinfunction "1_1") (pintype "passive"))
      (node (ref "C35") (pin "1") (pinfunction "1_1") (pintype "passive"))
      (node (ref "C37") (pin "1") (pinfunction "1_1") (pintype "passive"))
      (node (ref "C38") (pin "1") (pinfunction "1_1") (pintype "passive"))
      (node (ref "C4") (pin "2") (pinfunction "2_2") (pintype "passive"))
      (node (ref "C40") (pin "1") (pinfunction "1_1") (pintype "passive"))
      (node (ref "C41") (pin "1") (pinfunction "1_1") (pintype "passive"))
      (node (ref "C42") (pin "1") (pinfunction "1_1") (pintype "passive"))
      (node (ref "C43") (pin "1") (pinfunction "1_1") (pintype "passive"))
      (node (ref "C44") (pin "1") (pinfunction "1_1") (pintype "passive"))
      (node (ref "C45") (pin "2") (pinfunction "2_2") (pintype "passive"))
      (node (ref "C46") (pin "-") (pinfunction "-_-") (pintype "passive"))
      (node (ref "C47") (pin "2") (pinfunction "2_2") (pintype "passive"))
      (node (ref "C49") (pin "2") (pinfunction "2_2") (pintype "passive"))
      (node (ref "C5") (pin "2") (pinfunction "2_2") (pintype "passive"))
      (node (ref "C50") (pin "2") (pinfunction "2_2") (pintype "passive"))
      (node (ref "C51") (pin "1") (pinfunction "1_1") (pintype "passive"))
      (node (ref "C52") (pin "2") (pinfunction "2_2") (pintype "passive"))
      (node (ref "C53") (pin "2") (pinfunction "2_2") (pintype "passive"))
      (node (ref "C55") (pin "2") (pinfunction "2_2") (pintype "passive"))
      (node (ref "C57") (pin "2") (pinfunction "2_2") (pintype "passive"))
      (node (ref "C59") (pin "2") (pinfunction "2_2") (pintype "passive"))
      (node (ref "C6") (pin "2") (pinfunction "2_2") (pintype "passive"))
      (node (ref "C60") (pin "2") (pinfunction "2_2") (pintype "passive"))
      (node (ref "C61") (pin "2") (pinfunction "-_2") (pintype "passive"))
      (node (ref "C62") (pin "-") (pinfunction "-_-") (pintype "passive"))
      (node (ref "C63") (pin "2") (pinfunction "2_2") (pintype "passive"))
      (node (ref "C64") (pin "1") (pinfunction "1_1") (pintype "passive"))
      (node (ref "C66") (pin "1") (pinfunction "1_1") (pintype "passive"))
      (node (ref "C68") (pin "-") (pinfunction "-_-") (pintype "passive"))
      (node (ref "C70") (pin "2") (pinfunction "2_2") (pintype "passive"))
      (node (ref "C71") (pin "2") (pinfunction "2_2") (pintype "passive"))
      (node (ref "C72") (pin "2") (pinfunction "2_2") (pintype "passive"))
      (node (ref "C73") (pin "2") (pinfunction "2_2") (pintype "passive"))
      (node (ref "C75") (pin "2") (pinfunction "2_2") (pintype "passive"))
      (node (ref "C77") (pin "2") (pinfunction "2_2") (pintype "passive"))
      (node (ref "C79") (pin "2") (pinfunction "2_2") (pintype "passive"))
      (node (ref "C8") (pin "1") (pinfunction "1_1") (pintype "passive"))
      (node (ref "C80") (pin "2") (pinfunction "2_2") (pintype "passive"))
      (node (ref "C81") (pin "2") (pinfunction "-_2") (pintype "passive"))
      (node (ref "C82") (pin "-") (pinfunction "-_-") (pintype "passive"))
      (node (ref "C83") (pin "2") (pinfunction "2_2") (pintype "passive"))
      (node (ref "C84") (pin "1") (pinfunction "1_1") (pintype "passive"))
      (node (ref "C86") (pin "1") (pinfunction "1_1") (pintype "passive"))
      (node (ref "C9") (pin "2") (pinfunction "2_2") (pintype "passive"))
      (node (ref "CH1") (pin "GND") (pinfunction "GND_GND") (pintype "bidirectional"))
      (node (ref "CH2") (pin "GND") (pinfunction "GND_GND") (pintype "bidirectional"))
      (node (ref "D12") (pin "A") (pinfunction "A_A") (pintype "passive"))
      (node (ref "D2") (pin "A") (pinfunction "A_A") (pintype "passive"))
      (node (ref "D7") (pin "A") (pinfunction "A_A") (pintype "passive"))
      (node (ref "GND") (pin "1") (pinfunction "P$1_1") (pintype "bidirectional"))
      (node (ref "IC1") (pin "9") (pinfunction "GND2_9") (pintype "passive"))
      (node (ref "IC11") (pin "12") (pinfunction "GND_12") (pintype "passive"))
      (node (ref "IC11") (pin "21") (pinfunction "SYNC_21") (pintype "input"))
      (node (ref "IC11") (pin "23") (pinfunction "GND_23") (pintype "passive"))
      (node (ref "IC11") (pin "28") (pinfunction "GND_28") (pintype "passive"))
      (node (ref "IC11") (pin "TP") (pinfunction "GND_PAD_TP") (pintype "passive"))
      (node (ref "IC12") (pin "11") (pinfunction "V-_11") (pintype "power_in"))
      (node (ref "IC13") (pin "12") (pinfunction "GND_12") (pintype "passive"))
      (node (ref "IC13") (pin "21") (pinfunction "SYNC_21") (pintype "input"))
      (node (ref "IC13") (pin "23") (pinfunction "GND_23") (pintype "passive"))
      (node (ref "IC13") (pin "28") (pinfunction "GND_28") (pintype "passive"))
      (node (ref "IC13") (pin "TP") (pinfunction "GND_PAD_TP") (pintype "passive"))
      (node (ref "IC2") (pin "9") (pinfunction "GND_9") (pintype "passive"))
      (node (ref "IC2") (pin "TP") (pinfunction "TP_TP") (pintype "passive"))
      (node (ref "IC3") (pin "15") (pinfunction "GND2_15") (pintype "passive"))
      (node (ref "IC3") (pin "9") (pinfunction "GND2_2_9") (pintype "passive"))
      (node (ref "IC5") (pin "2") (pinfunction "GND_2") (pintype "passive"))
      (node (ref "IC6") (pin "2") (pinfunction "V-_2") (pintype "power_in"))
      (node (ref "IC7") (pin "3") (pinfunction "GND_3") (pintype "power_in"))
      (node (ref "IC8") (pin "47") (pinfunction "VSS_1_47") (pintype "bidirectional"))
      (node (ref "J3") (pin "1") (pinfunction "1_1") (pintype "passive"))
      (node (ref "J3") (pin "1.1") (pinfunction "1_1.1") (pintype "passive"))
      (node (ref "J5") (pin "1") (pinfunction "1_1") (pintype "passive"))
      (node (ref "J5") (pin "1.1") (pinfunction "1_1.1") (pintype "passive"))
      (node (ref "L1") (pin "2") (pinfunction "2_2") (pintype "passive"))
      (node (ref "LED1") (pin "CC") (pinfunction "C_CC") (pintype "passive"))
      (node (ref "LED2") (pin "CC") (pinfunction "C_CC") (pintype "passive"))
      (node (ref "Q3") (pin "3") (pinfunction "S_3") (pintype "passive"))
      (node (ref "Q8") (pin "3") (pinfunction "S_3") (pintype "passive"))
      (node (ref "R10") (pin "1") (pinfunction "1_1") (pintype "passive"))
      (node (ref "R15") (pin "1") (pinfunction "1_1") (pintype "passive"))
      (node (ref "R19") (pin "1") (pinfunction "1_1") (pintype "passive"))
      (node (ref "R21") (pin "2") (pinfunction "2_2") (pintype "passive"))
      (node (ref "R22") (pin "2") (pinfunction "2_2") (pintype "passive"))
      (node (ref "R30") (pin "1") (pinfunction "1_1") (pintype "passive"))
      (node (ref "R33") (pin "1") (pinfunction "1_1") (pintype "passive"))
      (node (ref "R37") (pin "1") (pinfunction "1_1") (pintype "passive"))
      (node (ref "R41") (pin "2") (pinfunction "2_2") (pintype "passive"))
      (node (ref "R42") (pin "1") (pinfunction "1_1") (pintype "passive"))
      (node (ref "R45") (pin "1") (pinfunction "1_1") (pintype "passive"))
      (node (ref "R46") (pin "1") (pinfunction "1_1") (pintype "passive"))
      (node (ref "R47") (pin "1") (pinfunction "1_1") (pintype "passive"))
      (node (ref "R5") (pin "1") (pinfunction "1_1") (pintype "passive"))
      (node (ref "R51") (pin "1") (pinfunction "1_1") (pintype "passive"))
      (node (ref "R54") (pin "1") (pinfunction "1_1") (pintype "passive"))
      (node (ref "R57") (pin "1") (pinfunction "1_1") (pintype "passive"))
      (node (ref "R6") (pin "1") (pinfunction "1_1") (pintype "passive"))
      (node (ref "R61") (pin "1") (pinfunction "1_1") (pintype "passive"))
      (node (ref "R65") (pin "2") (pinfunction "2_2") (pintype "passive"))
      (node (ref "R66") (pin "1") (pinfunction "1_1") (pintype "passive"))
      (node (ref "R69") (pin "1") (pinfunction "1_1") (pintype "passive"))
      (node (ref "R70") (pin "1") (pinfunction "1_1") (pintype "passive"))
      (node (ref "R71") (pin "1") (pinfunction "1_1") (pintype "passive"))
      (node (ref "R75") (pin "1") (pinfunction "1_1") (pintype "passive"))
      (node (ref "R8") (pin "1") (pinfunction "1_1") (pintype "passive"))
      (node (ref "SH2") (pin "2") (pinfunction "GND_B_2") (pintype "bidirectional"))
      (node (ref "TR1") (pin "4") (pinfunction "4_4") (pintype "passive"))
      (node (ref "X3") (pin "3") (pinfunction "S_3") (pintype "passive"))
      (node (ref "X4") (pin "1") (pinfunction "1_1") (pintype "passive"))
      (node (ref "X4") (pin "10") (pinfunction "1_10") (pintype "passive"))
      (node (ref "X4") (pin "2") (pinfunction "1_2") (pintype "passive"))
      (node (ref "X4") (pin "3") (pinfunction "1_3") (pintype "passive"))
      (node (ref "X4") (pin "4") (pinfunction "1_4") (pintype "passive"))
      (node (ref "X4") (pin "5") (pinfunction "1_5") (pintype "passive"))
      (node (ref "X4") (pin "6") (pinfunction "1_6") (pintype "passive"))
      (node (ref "X4") (pin "7") (pinfunction "1_7") (pintype "passive"))
      (node (ref "X4") (pin "8") (pinfunction "1_8") (pintype "passive"))
      (node (ref "X4") (pin "9") (pinfunction "1_9") (pintype "passive"))
      (node (ref "ZD1") (pin "A") (pinfunction "A_A") (pintype "passive"))
      (node (ref "ZD3") (pin "A") (pinfunction "A_A") (pintype "passive"))
      (node (ref "ZD5") (pin "A") (pinfunction "A_A") (pintype "passive"))
    )
    (net (code "33") (name "GNDIO") (class "Default")
      (node (ref "C17") (pin "2") (pinfunction "2_2") (pintype "passive"))
      (node (ref "C20") (pin "1") (pinfunction "1_1") (pintype "passive"))
      (node (ref "C7") (pin "2") (pinfunction "2_2") (pintype "passive"))
      (node (ref "IC1") (pin "8") (pinfunction "GND1_8") (pintype "passive"))
      (node (ref "IC3") (pin "2") (pinfunction "GND1_2_2") (pintype "passive"))
      (node (ref "IC3") (pin "8") (pinfunction "GND1_8") (pintype "passive"))
      (node (ref "IC4") (pin "4") (pinfunction "GND_4") (pintype "passive"))
      (node (ref "IC4") (pin "7") (pinfunction "WP_7") (pintype "input"))
      (node (ref "X2") (pin "11") (pinfunction "1_11") (pintype "passive"))
      (node (ref "X2") (pin "16") (pinfunction "1_16") (pintype "passive"))
      (node (ref "X2") (pin "20") (pinfunction "1_20") (pintype "passive"))
      (node (ref "X2") (pin "25") (pinfunction "1_25") (pintype "passive"))
      (node (ref "X2") (pin "7") (pinfunction "1_7") (pintype "passive"))
    )
    (net (code "34") (name "INTVCC1") (class "Default")
      (node (ref "C55") (pin "1") (pinfunction "1_1") (pintype "passive"))
      (node (ref "D6") (pin "A") (pinfunction "A_A") (pintype "passive"))
      (node (ref "IC11") (pin "2") (pinfunction "INTVCC_2") (pintype "passive"))
      (node (ref "R43") (pin "1") (pinfunction "1_1") (pintype "passive"))
      (node (ref "R44") (pin "2") (pinfunction "2_2") (pintype "passive"))
    )
    (net (code "35") (name "INTVCC2") (class "Default")
      (node (ref "C75") (pin "1") (pinfunction "1_1") (pintype "passive"))
      (node (ref "D11") (pin "A") (pinfunction "A_A") (pintype "passive"))
      (node (ref "IC13") (pin "2") (pinfunction "INTVCC_2") (pintype "passive"))
      (node (ref "R67") (pin "1") (pinfunction "1_1") (pintype "passive"))
      (node (ref "R68") (pin "2") (pinfunction "2_2") (pintype "passive"))
    )
    (net (code "36") (name "IRQ") (class "Default")
      (node (ref "IC1") (pin "10") (pinfunction "B6_10") (pintype "input"))
      (node (ref "IC8") (pin "33") (pinfunction "PA12_33") (pintype "bidirectional"))
    )
    (net (code "37") (name "I_MON#1") (class "Default")
      (node (ref "C42") (pin "2") (pinfunction "2_2") (pintype "passive"))
      (node (ref "IC8") (pin "19") (pinfunction "PB1_19") (pintype "bidirectional"))
      (node (ref "R25") (pin "1") (pinfunction "1_1") (pintype "passive"))
    )
    (net (code "38") (name "I_MON#2") (class "Default")
      (node (ref "C44") (pin "2") (pinfunction "2_2") (pintype "passive"))
      (node (ref "IC8") (pin "21") (pinfunction "PE8_21") (pintype "bidirectional"))
      (node (ref "R27") (pin "1") (pinfunction "1_1") (pintype "passive"))
    )
    (net (code "39") (name "I_MON1") (class "Default")
      (node (ref "C64") (pin "2") (pinfunction "2_2") (pintype "passive"))
      (node (ref "R25") (pin "2") (pinfunction "2_2") (pintype "passive"))
      (node (ref "R38") (pin "1") (pinfunction "1_1") (pintype "passive"))
    )
    (net (code "40") (name "I_MON2") (class "Default")
      (node (ref "C84") (pin "2") (pinfunction "2_2") (pintype "passive"))
      (node (ref "R27") (pin "2") (pinfunction "2_2") (pintype "passive"))
      (node (ref "R62") (pin "1") (pinfunction "1_1") (pintype "passive"))
    )
    (net (code "41") (name "I_SET#1") (class "Default")
      (node (ref "I_SET1") (pin "1") (pinfunction "1_1") (pintype "passive"))
      (node (ref "R32") (pin "1") (pinfunction "1_1") (pintype "passive"))
    )
    (net (code "42") (name "I_SET#2") (class "Default")
      (node (ref "I_SET2") (pin "1") (pinfunction "1_1") (pintype "passive"))
      (node (ref "R56") (pin "1") (pinfunction "1_1") (pintype "passive"))
    )
    (net (code "43") (name "I_SET_OUT#1") (class "Default")
      (node (ref "IC6") (pin "1") (pinfunction "I_1") (pintype "input"))
      (node (ref "IC8") (pin "45") (pinfunction "PB8_45") (pintype "bidirectional"))
      (node (ref "R14") (pin "2") (pinfunction "2_2") (pintype "passive"))
    )
    (net (code "44") (name "I_SET_OUT#2") (class "Default")
      (node (ref "IC6") (pin "3") (pinfunction "I_3") (pintype "input"))
      (node (ref "IC8") (pin "46") (pinfunction "PB9_46") (pintype "bidirectional"))
      (node (ref "R17") (pin "2") (pinfunction "2_2") (pintype "passive"))
    )
    (net (code "45") (name "MISO") (class "Default")
      (node (ref "IC1") (pin "11") (pinfunction "B5_11") (pintype "input"))
      (node (ref "IC8") (pin "26") (pinfunction "PB14_26") (pintype "bidirectional"))
    )
    (net (code "46") (name "MOSI") (class "Default")
      (node (ref "IC8") (pin "27") (pinfunction "PB15_27") (pintype "bidirectional"))
      (node (ref "RN1") (pin "5") (pinfunction "2_5") (pintype "passive"))
    )
    (net (code "47") (name "NRST") (class "Default")
      (node (ref "C36") (pin "1") (pinfunction "1_1") (pintype "passive"))
      (node (ref "IC8") (pin "7") (pinfunction "NRST_7") (pintype "input"))
      (node (ref "JP3") (pin "2") (pinfunction "2_2") (pintype "passive"))
      (node (ref "R20") (pin "2") (pinfunction "2_2") (pintype "passive"))
      (node (ref "RN2") (pin "3") (pinfunction "1_3") (pintype "passive"))
    )
    (net (code "48") (name "NSS") (class "Default")
      (node (ref "IC8") (pin "32") (pinfunction "PA11_32") (pintype "bidirectional"))
      (node (ref "RN1") (pin "6") (pinfunction "2_6") (pintype "passive"))
    )
    (net (code "49") (name "Net-(C4-Pad1)") (class "Default")
      (node (ref "C4") (pin "1") (pinfunction "1_1") (pintype "passive"))
      (node (ref "D1") (pin "A") (pinfunction "A_A") (pintype "passive"))
      (node (ref "R2") (pin "2") (pinfunction "2_2") (pintype "passive"))
    )
    (net (code "50") (name "Net-(C11-Pad2)") (class "Default")
      (node (ref "C11") (pin "2") (pinfunction "2_2") (pintype "passive"))
      (node (ref "R5") (pin "2") (pinfunction "2_2") (pintype "passive"))
    )
    (net (code "51") (name "Net-(C12-Pad1)") (class "Default")
      (node (ref "C12") (pin "1") (pinfunction "1_1") (pintype "passive"))
      (node (ref "C13") (pin "1") (pinfunction "1_1") (pintype "passive"))
      (node (ref "R4") (pin "2") (pinfunction "2_2") (pintype "passive"))
      (node (ref "R7") (pin "2") (pinfunction "2_2") (pintype "passive"))
      (node (ref "TR1") (pin "3") (pinfunction "3_3") (pintype "passive"))
    )
    (net (code "52") (name "Net-(C19-Pad2)") (class "Default")
      (node (ref "C19") (pin "2") (pinfunction "2_2") (pintype "passive"))
      (node (ref "R9") (pin "1") (pinfunction "1_1") (pintype "passive"))
    )
    (net (code "53") (name "Net-(C24-Pad1)") (class "Default")
      (node (ref "C24") (pin "1") (pinfunction "1_1") (pintype "passive"))
      (node (ref "C26") (pin "1") (pinfunction "1_1") (pintype "passive"))
      (node (ref "I_SET1") (pin "2") (pinfunction "2_2") (pintype "passive"))
      (node (ref "R14") (pin "1") (pinfunction "1_1") (pintype "passive"))
    )
    (net (code "54") (name "Net-(C24-Pad2)") (class "Default")
      (node (ref "C24") (pin "2") (pinfunction "2_2") (pintype "passive"))
      (node (ref "R16") (pin "1") (pinfunction "1_1") (pintype "passive"))
    )
    (net (code "55") (name "Net-(C30-Pad1)") (class "Default")
      (node (ref "C30") (pin "1") (pinfunction "1_1") (pintype "passive"))
      (node (ref "C31") (pin "1") (pinfunction "1_1") (pintype "passive"))
      (node (ref "I_SET2") (pin "2") (pinfunction "2_2") (pintype "passive"))
      (node (ref "R17") (pin "1") (pinfunction "1_1") (pintype "passive"))
    )
    (net (code "56") (name "Net-(C30-Pad2)") (class "Default")
      (node (ref "C30") (pin "2") (pinfunction "2_2") (pintype "passive"))
      (node (ref "R18") (pin "1") (pinfunction "1_1") (pintype "passive"))
    )
    (net (code "57") (name "Net-(C58-Pad2)") (class "Default")
      (node (ref "C58") (pin "2") (pinfunction "2_2") (pintype "passive"))
      (node (ref "R37") (pin "2") (pinfunction "2_2") (pintype "passive"))
    )
    (net (code "58") (name "Net-(C67-Pad1)") (class "Default")
      (node (ref "C67") (pin "1") (pinfunction "1_1") (pintype "passive"))
      (node (ref "R45") (pin "2") (pinfunction "2_2") (pintype "passive"))
    )
    (net (code "59") (name "Net-(C78-Pad2)") (class "Default")
      (node (ref "C78") (pin "2") (pinfunction "2_2") (pintype "passive"))
      (node (ref "R61") (pin "2") (pinfunction "2_2") (pintype "passive"))
    )
    (net (code "60") (name "Net-(C87-Pad1)") (class "Default")
      (node (ref "C87") (pin "1") (pinfunction "1_1") (pintype "passive"))
      (node (ref "R69") (pin "2") (pinfunction "2_2") (pintype "passive"))
    )
    (net (code "61") (name "Net-(D1-PadC)") (class "Default")
      (node (ref "D1") (pin "C") (pinfunction "C_C") (pintype "passive"))
      (node (ref "TR1") (pin "2") (pinfunction "2_2") (pintype "passive"))
    )
    (net (code "62") (name "Net-(IC1-B2)") (class "Default")
      (node (ref "IC1") (pin "14") (pinfunction "B2_14") (pintype "output"))
      (node (ref "RN1") (pin "1") (pinfunction "1_1") (pintype "passive"))
    )
    (net (code "63") (name "Net-(IC1-B3)") (class "Default")
      (node (ref "IC1") (pin "13") (pinfunction "B3_13") (pintype "output"))
      (node (ref "RN1") (pin "2") (pinfunction "1_2") (pintype "passive"))
    )
    (net (code "64") (name "Net-(IC1-B4)") (class "Default")
      (node (ref "IC1") (pin "12") (pinfunction "B4_12") (pintype "output"))
      (node (ref "RN1") (pin "3") (pinfunction "1_3") (pintype "passive"))
    )
    (net (code "65") (name "Net-(IC2-BOOT)") (class "Default")
      (node (ref "C10") (pin "2") (pinfunction "2_2") (pintype "passive"))
      (node (ref "IC2") (pin "1") (pinfunction "BOOT_1") (pintype "output"))
    )
    (net (code "66") (name "Net-(IC2-COMP)") (class "Default")
      (node (ref "C16") (pin "2") (pinfunction "2_2") (pintype "passive"))
      (node (ref "IC2") (pin "8") (pinfunction "COMP_8") (pintype "output"))
      (node (ref "R9") (pin "2") (pinfunction "2_2") (pintype "passive"))
    )
    (net (code "67") (name "Net-(IC2-EN)") (class "Default")
      (node (ref "IC2") (pin "3") (pinfunction "EN_3") (pintype "input"))
      (node (ref "R3") (pin "1") (pinfunction "1_1") (pintype "passive"))
      (node (ref "R6") (pin "2") (pinfunction "2_2") (pintype "passive"))
    )
    (net (code "68") (name "Net-(IC2-PH)") (class "Default")
      (node (ref "C10") (pin "1") (pinfunction "1_1") (pintype "passive"))
      (node (ref "C11") (pin "1") (pinfunction "1_1") (pintype "passive"))
      (node (ref "D2") (pin "C") (pinfunction "C_C") (pintype "passive"))
      (node (ref "IC2") (pin "10") (pinfunction "PH_10") (pintype "input"))
      (node (ref "TR1") (pin "1") (pinfunction "1_1") (pintype "passive"))
    )
    (net (code "69") (name "Net-(IC2-RT{slash}CLK)") (class "Default")
      (node (ref "IC2") (pin "5") (pinfunction "RT/CLK_5") (pintype "input"))
      (node (ref "R8") (pin "2") (pinfunction "2_2") (pintype "passive"))
    )
    (net (code "70") (name "Net-(IC2-SS{slash}TR)") (class "Default")
      (node (ref "C15") (pin "1") (pinfunction "1_1") (pintype "passive"))
      (node (ref "IC2") (pin "4") (pinfunction "SS/TR_4") (pintype "input"))
    )
    (net (code "71") (name "Net-(IC2-VSENSE)") (class "Default")
      (node (ref "IC2") (pin "7") (pinfunction "VSENSE_7") (pintype "input"))
      (node (ref "R10") (pin "2") (pinfunction "2_2") (pintype "passive"))
      (node (ref "R7") (pin "1") (pinfunction "1_1") (pintype "passive"))
    )
    (net (code "72") (name "Net-(IC3-B1)") (class "Default")
      (node (ref "IC3") (pin "14") (pinfunction "B1_14") (pintype "output"))
      (node (ref "RN1") (pin "4") (pinfunction "1_4") (pintype "passive"))
    )
    (net (code "73") (name "Net-(IC5-BYPASS)") (class "Default")
      (node (ref "C23") (pin "2") (pinfunction "2_2") (pintype "passive"))
      (node (ref "IC5") (pin "4") (pinfunction "BYPASS_4") (pintype "passive"))
    )
    (net (code "74") (name "Net-(IC6A-O)") (class "Default")
      (node (ref "IC6") (pin "6") (pinfunction "O_6") (pintype "output"))
      (node (ref "R16") (pin "2") (pinfunction "2_2") (pintype "passive"))
    )
    (net (code "75") (name "Net-(IC6B-O)") (class "Default")
      (node (ref "IC6") (pin "4") (pinfunction "O_4") (pintype "output"))
      (node (ref "R18") (pin "2") (pinfunction "2_2") (pintype "passive"))
    )
    (net (code "76") (name "Net-(IC7-IO1)") (class "Default")
      (node (ref "IC7") (pin "1") (pinfunction "IO1_1") (pintype "bidirectional"))
      (node (ref "RN2") (pin "8") (pinfunction "2_8") (pintype "passive"))
      (node (ref "X3") (pin "6") (pinfunction "S_6") (pintype "passive"))
    )
    (net (code "77") (name "Net-(IC7-IO2)") (class "Default")
      (node (ref "IC7") (pin "2") (pinfunction "IO2_2") (pintype "bidirectional"))
      (node (ref "RN2") (pin "6") (pinfunction "2_6") (pintype "passive"))
      (node (ref "X3") (pin "5") (pinfunction "S_5") (pintype "passive"))
    )
    (net (code "78") (name "Net-(IC8-PB5)") (class "Default")
      (node (ref "IC8") (pin "41") (pinfunction "PB5_41") (pintype "bidirectional"))
      (node (ref "OE#1") (pin "1") (pinfunction "1_1") (pintype "passive"))
    )
    (net (code "79") (name "Net-(IC8-PB6)") (class "Default")
      (node (ref "IC8") (pin "42") (pinfunction "PB6_42") (pintype "bidirectional"))
      (node (ref "OE#2") (pin "1") (pinfunction "1_1") (pintype "passive"))
    )
    (net (code "80") (name "Net-(IC8-PF0-OSC_IN)") (class "Default")
      (node (ref "C32") (pin "2") (pinfunction "2_2") (pintype "passive"))
      (node (ref "IC8") (pin "5") (pinfunction "PF0-OSC_IN_5") (pintype "bidirectional"))
      (node (ref "Y1") (pin "3") (pinfunction "2_3") (pintype "passive"))
    )
    (net (code "81") (name "Net-(IC8-PF1-OSC_OUT)") (class "Default")
      (node (ref "C33") (pin "2") (pinfunction "2_2") (pintype "passive"))
      (node (ref "IC8") (pin "6") (pinfunction "PF1-OSC_OUT_6") (pintype "bidirectional"))
      (node (ref "Y1") (pin "1") (pinfunction "1_1") (pintype "passive"))
    )
    (net (code "82") (name "Net-(IC10A-+IN)") (class "Default")
      (node (ref "IC10") (pin "3") (pinfunction "+IN_3") (pintype "input"))
      (node (ref "R56") (pin "2") (pinfunction "2_2") (pintype "passive"))
      (node (ref "R57") (pin "2") (pinfunction "2_2") (pintype "passive"))
    )
    (net (code "83") (name "Net-(IC10A--IN)") (class "Default")
      (node (ref "C69") (pin "2") (pinfunction "2_2") (pintype "passive"))
      (node (ref "IC10") (pin "2") (pinfunction "-IN_2") (pintype "input"))
      (node (ref "R54") (pin "2") (pinfunction "2_2") (pintype "passive"))
      (node (ref "R55") (pin "1") (pinfunction "1_1") (pintype "passive"))
    )
    (net (code "84") (name "Net-(IC10A-OUT)") (class "Default")
      (node (ref "C69") (pin "1") (pinfunction "1_1") (pintype "passive"))
      (node (ref "IC10") (pin "1") (pinfunction "OUT_1") (pintype "output"))
      (node (ref "IC13") (pin "14") (pinfunction "CTRL1_14") (pintype "input"))
      (node (ref "R55") (pin "2") (pinfunction "2_2") (pintype "passive"))
    )
    (net (code "85") (name "Net-(IC10B-+IN)") (class "Default")
      (node (ref "IC10") (pin "5") (pinfunction "+IN_5") (pintype "input"))
      (node (ref "R32") (pin "2") (pinfunction "2_2") (pintype "passive"))
      (node (ref "R33") (pin "2") (pinfunction "2_2") (pintype "passive"))
    )
    (net (code "86") (name "Net-(IC10B--IN)") (class "Default")
      (node (ref "C48") (pin "2") (pinfunction "2_2") (pintype "passive"))
      (node (ref "IC10") (pin "6") (pinfunction "-IN_6") (pintype "input"))
      (node (ref "R30") (pin "2") (pinfunction "2_2") (pintype "passive"))
      (node (ref "R31") (pin "1") (pinfunction "1_1") (pintype "passive"))
    )
    (net (code "87") (name "Net-(IC10B-OUT)") (class "Default")
      (node (ref "C48") (pin "1") (pinfunction "1_1") (pintype "passive"))
      (node (ref "IC10") (pin "7") (pinfunction "OUT_7") (pintype "output"))
      (node (ref "IC11") (pin "14") (pinfunction "CTRL1_14") (pintype "input"))
      (node (ref "R31") (pin "2") (pinfunction "2_2") (pintype "passive"))
    )
    (net (code "88") (name "Net-(IC11-BG)") (class "Default")
      (node (ref "IC11") (pin "1") (pinfunction "BG_1") (pintype "output"))
      (node (ref "Q3") (pin "1") (pinfunction "G_1") (pintype "passive"))
    )
    (net (code "89") (name "Net-(IC11-BOOST)") (class "Default")
      (node (ref "C54") (pin "1") (pinfunction "1_1") (pintype "passive"))
      (node (ref "D6") (pin "C") (pinfunction "C_C") (pintype "passive"))
      (node (ref "IC11") (pin "27") (pinfunction "BOOST_27") (pintype "passive"))
    )
    (net (code "90") (name "Net-(IC11-ISMON)") (class "Default")
      (node (ref "IC11") (pin "19") (pinfunction "ISMON_19") (pintype "output"))
      (node (ref "R38") (pin "2") (pinfunction "2_2") (pintype "passive"))
    )
    (net (code "91") (name "Net-(IC11-PWM)") (class "Default")
      (node (ref "IC11") (pin "22") (pinfunction "PWM_22") (pintype "input"))
      (node (ref "R43") (pin "2") (pinfunction "2_2") (pintype "passive"))
    )
    (net (code "92") (name "Net-(IC11-RT)") (class "Default")
      (node (ref "IC11") (pin "20") (pinfunction "RT_20") (pintype "input"))
      (node (ref "R42") (pin "2") (pinfunction "2_2") (pintype "passive"))
    )
    (net (code "93") (name "Net-(IC11-SENSE+)") (class "Default")
      (node (ref "C65") (pin "1") (pinfunction "1_1") (pintype "passive"))
      (node (ref "IC11") (pin "17") (pinfunction "SENSE+_17") (pintype "input"))
      (node (ref "R35") (pin "1") (pinfunction "1_1") (pintype "passive"))
    )
    (net (code "94") (name "Net-(IC11-SENSE-)") (class "Default")
      (node (ref "C65") (pin "2") (pinfunction "2_2") (pintype "passive"))
      (node (ref "IC11") (pin "16") (pinfunction "SENSE-_16") (pintype "input"))
      (node (ref "R36") (pin "1") (pinfunction "1_1") (pintype "passive"))
    )
    (net (code "95") (name "Net-(IC11-SS)") (class "Default")
      (node (ref "C66") (pin "2") (pinfunction "2_2") (pintype "passive"))
      (node (ref "IC11") (pin "15") (pinfunction "SS_15") (pintype "input"))
    )
    (net (code "96") (name "Net-(IC11-SW)") (class "Default")
      (node (ref "C54") (pin "2") (pinfunction "2_2") (pintype "passive"))
      (node (ref "C58") (pin "1") (pinfunction "1_1") (pintype "passive"))
      (node (ref "D7") (pin "C") (pinfunction "C_C") (pintype "passive"))
      (node (ref "IC11") (pin "26") (pinfunction "SW_26") (pintype "output"))
      (node (ref "L2") (pin "1") (pinfunction "1_1") (pintype "passive"))
      (node (ref "Q2") (pin "3") (pinfunction "S_3") (pintype "passive"))
      (node (ref "Q3") (pin "2") (pinfunction "D_2") (pintype "passive"))
    )
    (net (code "97") (name "Net-(IC11-TG)") (class "Default")
      (node (ref "IC11") (pin "25") (pinfunction "TG_25") (pintype "output"))
      (node (ref "Q2") (pin "1") (pinfunction "G_1") (pintype "passive"))
    )
    (net (code "98") (name "Net-(IC11-VC)") (class "Default")
      (node (ref "C67") (pin "2") (pinfunction "2_2") (pintype "passive"))
      (node (ref "IC11") (pin "18") (pinfunction "VC_18") (pintype "passive"))
    )
    (net (code "99") (name "Net-(IC11-VIN)") (class "Default")
      (node (ref "C49") (pin "1") (pinfunction "1_1") (pintype "passive"))
      (node (ref "D3") (pin "C") (pinfunction "C_C") (pintype "passive"))
      (node (ref "D5") (pin "C") (pinfunction "C_C") (pintype "passive"))
      (node (ref "IC11") (pin "3") (pinfunction "VIN_3") (pintype "passive"))
    )
    (net (code "100") (name "Net-(IC11-~{FAULT})") (class "Default")
      (node (ref "IC11") (pin "9") (pinfunction "~{FAULT}_9") (pintype "output"))
      (node (ref "R44") (pin "1") (pinfunction "1_1") (pintype "passive"))
    )
    (net (code "101") (name "Net-(IC12A-+IN)") (class "Default")
      (node (ref "IC12") (pin "3") (pinfunction "+IN_3") (pintype "input"))
      (node (ref "R74") (pin "1") (pinfunction "1_1") (pintype "passive"))
      (node (ref "R75") (pin "2") (pinfunction "2_2") (pintype "passive"))
    )
    (net (code "102") (name "Net-(IC12A--IN)") (class "Default")
      (node (ref "IC12") (pin "13") (pinfunction "-IN_13") (pintype "input"))
      (node (ref "IC12") (pin "14") (pinfunction "OUT_14") (pintype "output"))
      (node (ref "IC12") (pin "2") (pinfunction "-IN_2") (pintype "input"))
    )
    (net (code "103") (name "Net-(IC12B-+IN)") (class "Default")
      (node (ref "IC12") (pin "5") (pinfunction "+IN_5") (pintype "input"))
      (node (ref "R50") (pin "1") (pinfunction "1_1") (pintype "passive"))
      (node (ref "R51") (pin "2") (pinfunction "2_2") (pintype "passive"))
    )
    (net (code "104") (name "Net-(IC12B--IN)") (class "Default")
      (node (ref "IC12") (pin "6") (pinfunction "-IN_6") (pintype "input"))
      (node (ref "IC12") (pin "8") (pinfunction "OUT_8") (pintype "output"))
      (node (ref "IC12") (pin "9") (pinfunction "-IN_9") (pintype "input"))
    )
    (net (code "105") (name "Net-(IC13-BG)") (class "Default")
      (node (ref "IC13") (pin "1") (pinfunction "BG_1") (pintype "output"))
      (node (ref "Q8") (pin "1") (pinfunction "G_1") (pintype "passive"))
    )
    (net (code "106") (name "Net-(IC13-BOOST)") (class "Default")
      (node (ref "C74") (pin "1") (pinfunction "1_1") (pintype "passive"))
      (node (ref "D11") (pin "C") (pinfunction "C_C") (pintype "passive"))
      (node (ref "IC13") (pin "27") (pinfunction "BOOST_27") (pintype "passive"))
    )
    (net (code "107") (name "Net-(IC13-ISMON)") (class "Default")
      (node (ref "IC13") (pin "19") (pinfunction "ISMON_19") (pintype "output"))
      (node (ref "R62") (pin "2") (pinfunction "2_2") (pintype "passive"))
    )
    (net (code "108") (name "Net-(IC13-PWM)") (class "Default")
      (node (ref "IC13") (pin "22") (pinfunction "PWM_22") (pintype "input"))
      (node (ref "R67") (pin "2") (pinfunction "2_2") (pintype "passive"))
    )
    (net (code "109") (name "Net-(IC13-RT)") (class "Default")
      (node (ref "IC13") (pin "20") (pinfunction "RT_20") (pintype "input"))
      (node (ref "R66") (pin "2") (pinfunction "2_2") (pintype "passive"))
    )
    (net (code "110") (name "Net-(IC13-SENSE+)") (class "Default")
      (node (ref "C85") (pin "1") (pinfunction "1_1") (pintype "passive"))
      (node (ref "IC13") (pin "17") (pinfunction "SENSE+_17") (pintype "input"))
      (node (ref "R59") (pin "1") (pinfunction "1_1") (pintype "passive"))
    )
    (net (code "111") (name "Net-(IC13-SENSE-)") (class "Default")
      (node (ref "C85") (pin "2") (pinfunction "2_2") (pintype "passive"))
      (node (ref "IC13") (pin "16") (pinfunction "SENSE-_16") (pintype "input"))
      (node (ref "R60") (pin "1") (pinfunction "1_1") (pintype "passive"))
    )
    (net (code "112") (name "Net-(IC13-SS)") (class "Default")
      (node (ref "C86") (pin "2") (pinfunction "2_2") (pintype "passive"))
      (node (ref "IC13") (pin "15") (pinfunction "SS_15") (pintype "input"))
    )
    (net (code "113") (name "Net-(IC13-SW)") (class "Default")
      (node (ref "C74") (pin "2") (pinfunction "2_2") (pintype "passive"))
      (node (ref "C78") (pin "1") (pinfunction "1_1") (pintype "passive"))
      (node (ref "D12") (pin "C") (pinfunction "C_C") (pintype "passive"))
      (node (ref "IC13") (pin "26") (pinfunction "SW_26") (pintype "output"))
      (node (ref "L4") (pin "1") (pinfunction "1_1") (pintype "passive"))
      (node (ref "Q7") (pin "3") (pinfunction "S_3") (pintype "passive"))
      (node (ref "Q8") (pin "2") (pinfunction "D_2") (pintype "passive"))
    )
    (net (code "114") (name "Net-(IC13-TG)") (class "Default")
      (node (ref "IC13") (pin "25") (pinfunction "TG_25") (pintype "output"))
      (node (ref "Q7") (pin "1") (pinfunction "G_1") (pintype "passive"))
    )
    (net (code "115") (name "Net-(IC13-VC)") (class "Default")
      (node (ref "C87") (pin "2") (pinfunction "2_2") (pintype "passive"))
      (node (ref "IC13") (pin "18") (pinfunction "VC_18") (pintype "passive"))
    )
    (net (code "116") (name "Net-(IC13-VIN)") (class "Default")
      (node (ref "C70") (pin "1") (pinfunction "1_1") (pintype "passive"))
      (node (ref "D10") (pin "C") (pinfunction "C_C") (pintype "passive"))
      (node (ref "D8") (pin "C") (pinfunction "C_C") (pintype "passive"))
      (node (ref "IC13") (pin "3") (pinfunction "VIN_3") (pintype "passive"))
    )
    (net (code "117") (name "Net-(IC13-~{FAULT})") (class "Default")
      (node (ref "IC13") (pin "9") (pinfunction "~{FAULT}_9") (pintype "output"))
      (node (ref "R68") (pin "1") (pinfunction "1_1") (pintype "passive"))
    )
    (net (code "118") (name "Net-(L1A-1)") (class "Default")
      (node (ref "C1") (pin "2") (pinfunction "2_2") (pintype "passive"))
      (node (ref "L1") (pin "3") (pinfunction "1_3") (pintype "passive"))
      (node (ref "R1") (pin "2") (pinfunction "2_2") (pintype "passive"))
      (node (ref "X1") (pin "1") (pinfunction "1_1") (pintype "passive"))
    )
    (net (code "119") (name "Net-(L2-Pad2)") (class "Default")
      (node (ref "L2") (pin "2") (pinfunction "2_2") (pintype "passive"))
      (node (ref "R34") (pin "1") (pinfunction "1_1") (pintype "passive"))
    )
    (net (code "120") (name "Net-(L4-Pad2)") (class "Default")
      (node (ref "L4") (pin "2") (pinfunction "2_2") (pintype "passive"))
      (node (ref "R58") (pin "1") (pinfunction "1_1") (pintype "passive"))
    )
    (net (code "121") (name "Net-(LED1-AG)") (class "Default")
      (node (ref "LED1") (pin "GREEN") (pinfunction "AG_GREEN") (pintype "passive"))
      (node (ref "Q4") (pin "2") (pinfunction "S_2") (pintype "passive"))
    )
    (net (code "122") (name "Net-(LED1-AR)") (class "Default")
      (node (ref "LED1") (pin "RED") (pinfunction "AR_RED") (pintype "passive"))
      (node (ref "R49") (pin "1") (pinfunction "1_1") (pintype "passive"))
    )
    (net (code "123") (name "Net-(LED2-AG)") (class "Default")
      (node (ref "LED2") (pin "GREEN") (pinfunction "AG_GREEN") (pintype "passive"))
      (node (ref "Q9") (pin "2") (pinfunction "S_2") (pintype "passive"))
    )
    (net (code "124") (name "Net-(LED2-AR)") (class "Default")
      (node (ref "LED2") (pin "RED") (pinfunction "AR_RED") (pintype "passive"))
      (node (ref "R73") (pin "1") (pinfunction "1_1") (pintype "passive"))
    )
    (net (code "125") (name "Net-(Q1-D-Pad2)") (class "Default")
      (node (ref "Q1") (pin "2") (pinfunction "D_2") (pintype "passive"))
      (node (ref "Q1") (pin "4") (pinfunction "D_4") (pintype "passive"))
      (node (ref "R28") (pin "2") (pinfunction "2_2") (pintype "passive"))
    )
    (net (code "126") (name "Net-(Q1-G)") (class "Default")
      (node (ref "D4") (pin "C") (pinfunction "C_C") (pintype "passive"))
      (node (ref "Q1") (pin "1") (pinfunction "G_1") (pintype "passive"))
      (node (ref "R29") (pin "2") (pinfunction "2_2") (pintype "passive"))
      (node (ref "ZD2") (pin "C") (pinfunction "C_C") (pintype "passive"))
    )
    (net (code "127") (name "Net-(Q1-S)") (class "Default")
      (node (ref "D3") (pin "A") (pinfunction "A_A") (pintype "passive"))
      (node (ref "D4") (pin "A") (pinfunction "A_A") (pintype "passive"))
      (node (ref "Q1") (pin "3") (pinfunction "S_3") (pintype "passive"))
    )
    (net (code "128") (name "Net-(Q4-D)") (class "Default")
      (node (ref "Q4") (pin "3") (pinfunction "D_3") (pintype "passive"))
      (node (ref "Q5") (pin "3") (pinfunction "D_3") (pintype "passive"))
    )
    (net (code "129") (name "Net-(Q6-D-Pad2)") (class "Default")
      (node (ref "Q6") (pin "2") (pinfunction "D_2") (pintype "passive"))
      (node (ref "Q6") (pin "4") (pinfunction "D_4") (pintype "passive"))
      (node (ref "R52") (pin "2") (pinfunction "2_2") (pintype "passive"))
    )
    (net (code "130") (name "Net-(Q6-G)") (class "Default")
      (node (ref "D9") (pin "C") (pinfunction "C_C") (pintype "passive"))
      (node (ref "Q6") (pin "1") (pinfunction "G_1") (pintype "passive"))
      (node (ref "R53") (pin "2") (pinfunction "2_2") (pintype "passive"))
      (node (ref "ZD4") (pin "C") (pinfunction "C_C") (pintype "passive"))
    )
    (net (code "131") (name "Net-(Q6-S)") (class "Default")
      (node (ref "D8") (pin "A") (pinfunction "A_A") (pintype "passive"))
      (node (ref "D9") (pin "A") (pinfunction "A_A") (pintype "passive"))
      (node (ref "Q6") (pin "3") (pinfunction "S_3") (pintype "passive"))
    )
    (net (code "132") (name "Net-(Q10-D)") (class "Default")
      (node (ref "Q10") (pin "3") (pinfunction "D_3") (pintype "passive"))
      (node (ref "Q9") (pin "3") (pinfunction "D_3") (pintype "passive"))
    )
    (net (code "133") (name "Net-(R34-Pad1S)") (class "Default")
      (node (ref "R34") (pin "1S") (pinfunction "1S_1S") (pintype "passive"))
      (node (ref "R35") (pin "2") (pinfunction "2_2") (pintype "passive"))
    )
    (net (code "134") (name "Net-(R34-Pad2S)") (class "Default")
      (node (ref "R34") (pin "2S") (pinfunction "2S_2S") (pintype "passive"))
      (node (ref "R36") (pin "2") (pinfunction "2_2") (pintype "passive"))
    )
    (net (code "135") (name "Net-(R58-Pad1S)") (class "Default")
      (node (ref "R58") (pin "1S") (pinfunction "1S_1S") (pintype "passive"))
      (node (ref "R59") (pin "2") (pinfunction "2_2") (pintype "passive"))
    )
    (net (code "136") (name "Net-(R58-Pad2S)") (class "Default")
      (node (ref "R58") (pin "2S") (pinfunction "2S_2S") (pintype "passive"))
      (node (ref "R60") (pin "2") (pinfunction "2_2") (pintype "passive"))
    )
    (net (code "137") (name "Net-(X1B-1)") (class "Default")
      (node (ref "C1") (pin "1") (pinfunction "1_1") (pintype "passive"))
      (node (ref "L1") (pin "1") (pinfunction "1_1") (pintype "passive"))
      (node (ref "R1") (pin "1") (pinfunction "1_1") (pintype "passive"))
      (node (ref "X1") (pin "2") (pinfunction "1_2") (pintype "passive"))
    )
    (net (code "138") (name "Net-(X3A-S)") (class "Default")
      (node (ref "JP2") (pin "2") (pinfunction "2_2") (pintype "passive"))
      (node (ref "R19") (pin "2") (pinfunction "2_2") (pintype "passive"))
      (node (ref "X3") (pin "1") (pinfunction "S_1") (pintype "passive"))
    )
    (net (code "139") (name "OE#1") (class "Default")
      (node (ref "IC11") (pin "4") (pinfunction "EV/UVLO_4") (pintype "input"))
      (node (ref "OE#1") (pin "2") (pinfunction "2_2") (pintype "passive"))
      (node (ref "Q4") (pin "1") (pinfunction "G_1") (pintype "passive"))
    )
    (net (code "140") (name "OE#2") (class "Default")
      (node (ref "IC13") (pin "4") (pinfunction "EV/UVLO_4") (pintype "input"))
      (node (ref "OE#2") (pin "2") (pinfunction "2_2") (pintype "passive"))
      (node (ref "Q9") (pin "1") (pinfunction "G_1") (pintype "passive"))
    )
    (net (code "141") (name "OE_SYNC") (class "Default")
      (node (ref "IC8") (pin "36") (pinfunction "PF7_36") (pintype "bidirectional"))
      (node (ref "RN1") (pin "8") (pinfunction "2_8") (pintype "passive"))
    )
    (net (code "142") (name "PE") (class "Default")
      (node (ref "C2") (pin "2") (pinfunction "2_2") (pintype "passive"))
      (node (ref "C3") (pin "1") (pinfunction "1_1") (pintype "passive"))
      (node (ref "C56") (pin "1") (pinfunction "1_1") (pintype "passive"))
      (node (ref "C63") (pin "1") (pinfunction "1_1") (pintype "passive"))
      (node (ref "C76") (pin "1") (pinfunction "1_1") (pintype "passive"))
      (node (ref "C83") (pin "1") (pinfunction "1_1") (pintype "passive"))
      (node (ref "J1") (pin "1") (pinfunction "P$1_1") (pintype "bidirectional"))
      (node (ref "J1") (pin "2") (pinfunction "P$1_2") (pintype "bidirectional"))
    )
    (net (code "143") (name "PWRGOOD") (class "Default")
      (node (ref "IC2") (pin "6") (pinfunction "PWRGD_6") (pintype "output"))
      (node (ref "IC8") (pin "40") (pinfunction "PB4_40") (pintype "bidirectional"))
    )
    (net (code "144") (name "SCLK") (class "Default")
      (node (ref "IC8") (pin "28") (pinfunction "PD8_28") (pintype "bidirectional"))
      (node (ref "RN1") (pin "7") (pinfunction "2_7") (pintype "passive"))
    )
    (net (code "145") (name "SWCLK") (class "Default")
      (node (ref "IC8") (pin "37") (pinfunction "PA14_37") (pintype "bidirectional"))
      (node (ref "RN2") (pin "2") (pinfunction "1_2") (pintype "passive"))
    )
    (net (code "146") (name "SWDIO") (class "Default")
      (node (ref "IC8") (pin "34") (pinfunction "PA13_34") (pintype "bidirectional"))
      (node (ref "RN2") (pin "4") (pinfunction "1_4") (pintype "passive"))
    )
    (net (code "147") (name "SWO") (class "Default")
      (node (ref "IC8") (pin "39") (pinfunction "PB3_39") (pintype "bidirectional"))
      (node (ref "RN2") (pin "1") (pinfunction "1_1") (pintype "passive"))
    )
    (net (code "148") (name "TCK") (class "Default")
      (node (ref "IC7") (pin "5") (pinfunction "IO4_5") (pintype "bidirectional"))
      (node (ref "RN2") (pin "7") (pinfunction "2_7") (pintype "passive"))
      (node (ref "X3") (pin "2") (pinfunction "S_2") (pintype "passive"))
    )
    (net (code "149") (name "TEMP#1") (class "Default")
      (node (ref "C34") (pin "2") (pinfunction "2_2") (pintype "passive"))
      (node (ref "IC8") (pin "10") (pinfunction "PA0_10") (pintype "bidirectional"))
      (node (ref "NTC1") (pin "2") (pinfunction "P$2_2") (pintype "bidirectional"))
      (node (ref "R21") (pin "1") (pinfunction "1_1") (pintype "passive"))
    )
    (net (code "150") (name "TEMP#2") (class "Default")
      (node (ref "C35") (pin "2") (pinfunction "2_2") (pintype "passive"))
      (node (ref "IC8") (pin "14") (pinfunction "PA4_14") (pintype "bidirectional"))
      (node (ref "NTC2") (pin "2") (pinfunction "P$2_2") (pintype "bidirectional"))
      (node (ref "R22") (pin "1") (pinfunction "1_1") (pintype "passive"))
    )
    (net (code "151") (name "TMS") (class "Default")
      (node (ref "IC7") (pin "4") (pinfunction "IO3_4") (pintype "bidirectional"))
      (node (ref "RN2") (pin "5") (pinfunction "2_5") (pintype "passive"))
      (node (ref "X3") (pin "4") (pinfunction "S_4") (pintype "passive"))
    )
    (net (code "152") (name "UART_RX") (class "Default")
      (node (ref "IC3") (pin "12") (pinfunction "B3_12") (pintype "output"))
      (node (ref "IC8") (pin "31") (pinfunction "PA10_31") (pintype "bidirectional"))
    )
    (net (code "153") (name "UART_TX") (class "Default")
      (node (ref "IC3") (pin "11") (pinfunction "B4_11") (pintype "input"))
      (node (ref "IC8") (pin "30") (pinfunction "PA9_30") (pintype "bidirectional"))
      (node (ref "TX_PU") (pin "1") (pinfunction "1_1") (pintype "passive"))
    )
    (net (code "154") (name "U_MON#1") (class "Default")
      (node (ref "C41") (pin "2") (pinfunction "2_2") (pintype "passive"))
      (node (ref "IC8") (pin "18") (pinfunction "PB0_18") (pintype "bidirectional"))
      (node (ref "R24") (pin "1") (pinfunction "1_1") (pintype "passive"))
    )
    (net (code "155") (name "U_MON#2") (class "Default")
      (node (ref "C43") (pin "2") (pinfunction "2_2") (pintype "passive"))
      (node (ref "IC8") (pin "20") (pinfunction "PB2_20") (pintype "bidirectional"))
      (node (ref "R26") (pin "1") (pinfunction "1_1") (pintype "passive"))
    )
    (net (code "156") (name "U_MON1") (class "Default")
      (node (ref "R24") (pin "2") (pinfunction "2_2") (pintype "passive"))
      (node (ref "R40") (pin "1") (pinfunction "1_1") (pintype "passive"))
      (node (ref "R47") (pin "2") (pinfunction "2_2") (pintype "passive"))
    )
    (net (code "157") (name "U_MON2") (class "Default")
      (node (ref "R26") (pin "2") (pinfunction "2_2") (pintype "passive"))
      (node (ref "R64") (pin "1") (pinfunction "1_1") (pintype "passive"))
      (node (ref "R71") (pin "2") (pinfunction "2_2") (pintype "passive"))
    )
    (net (code "158") (name "U_SET#1") (class "Default")
      (node (ref "R48") (pin "1") (pinfunction "1_1") (pintype "passive"))
      (node (ref "U_SET1") (pin "1") (pinfunction "1_1") (pintype "passive"))
    )
    (net (code "159") (name "U_SET#2") (class "Default")
      (node (ref "R72") (pin "1") (pinfunction "1_1") (pintype "passive"))
      (node (ref "U_SET2") (pin "1") (pinfunction "1_1") (pintype "passive"))
    )
    (net (code "160") (name "U_SET_OUT#1") (class "Default")
      (node (ref "IC8") (pin "16") (pinfunction "PA6_16") (pintype "bidirectional"))
      (node (ref "U_SET1") (pin "2") (pinfunction "2_2") (pintype "passive"))
    )
    (net (code "161") (name "U_SET_OUT#2") (class "Default")
      (node (ref "IC8") (pin "15") (pinfunction "PA5_15") (pintype "bidirectional"))
      (node (ref "U_SET2") (pin "2") (pinfunction "2_2") (pintype "passive"))
    )
    (net (code "162") (name "V+") (class "Default")
      (node (ref "C17") (pin "1") (pinfunction "1_1") (pintype "passive"))
      (node (ref "C20") (pin "2") (pinfunction "2_2") (pintype "passive"))
      (node (ref "C7") (pin "1") (pinfunction "1_1") (pintype "passive"))
      (node (ref "IC1") (pin "1") (pinfunction "VDD1_1") (pintype "passive"))
      (node (ref "IC3") (pin "1") (pinfunction "VDD1_1") (pintype "passive"))
      (node (ref "IC4") (pin "8") (pinfunction "VCC_8") (pintype "power_in"))
      (node (ref "R11") (pin "1") (pinfunction "1_1") (pintype "passive"))
      (node (ref "R12") (pin "1") (pinfunction "1_1") (pintype "passive"))
      (node (ref "R13") (pin "1") (pinfunction "1_1") (pintype "passive"))
      (node (ref "X2") (pin "1") (pinfunction "1_1") (pintype "passive"))
    )
    (net (code "163") (name "VDDA") (class "Default")
      (node (ref "C37") (pin "2") (pinfunction "2_2") (pintype "passive"))
      (node (ref "C38") (pin "2") (pinfunction "2_2") (pintype "passive"))
      (node (ref "FB1") (pin "P$2") (pinfunction "2_P$2") (pintype "passive"))
      (node (ref "IC8") (pin "24") (pinfunction "VDDSD_24") (pintype "passive"))
    )
    (net (code "164") (name "VOUT1+") (class "Default")
      (node (ref "C59") (pin "1") (pinfunction "1_1") (pintype "passive"))
      (node (ref "C60") (pin "1") (pinfunction "1_1") (pintype "passive"))
      (node (ref "C62") (pin "+") (pinfunction "+_+") (pintype "passive"))
      (node (ref "L3") (pin "1") (pinfunction "1_1") (pintype "passive"))
      (node (ref "R34") (pin "2") (pinfunction "2_2") (pintype "passive"))
      (node (ref "R39") (pin "2") (pinfunction "2_2") (pintype "passive"))
      (node (ref "R40") (pin "2") (pinfunction "2_2") (pintype "passive"))
      (node (ref "ZD2") (pin "A") (pinfunction "A_A") (pintype "passive"))
    )
    (net (code "165") (name "VOUT2+") (class "Default")
      (node (ref "C79") (pin "1") (pinfunction "1_1") (pintype "passive"))
      (node (ref "C80") (pin "1") (pinfunction "1_1") (pintype "passive"))
      (node (ref "C82") (pin "+") (pinfunction "+_+") (pintype "passive"))
      (node (ref "L5") (pin "1") (pinfunction "1_1") (pintype "passive"))
      (node (ref "R58") (pin "2") (pinfunction "2_2") (pintype "passive"))
      (node (ref "R63") (pin "2") (pinfunction "2_2") (pintype "passive"))
      (node (ref "R64") (pin "2") (pinfunction "2_2") (pintype "passive"))
      (node (ref "ZD4") (pin "A") (pinfunction "A_A") (pintype "passive"))
    )
    (net (code "166") (name "VOUT_LC1+") (class "Default")
      (node (ref "C56") (pin "2") (pinfunction "2_2") (pintype "passive"))
      (node (ref "C57") (pin "1") (pinfunction "1_1") (pintype "passive"))
      (node (ref "C61") (pin "1") (pinfunction "+_1") (pintype "passive"))
      (node (ref "CH1") (pin "TIP") (pinfunction "TIP_TIP") (pintype "bidirectional"))
      (node (ref "J2") (pin "1") (pinfunction "1_1") (pintype "passive"))
      (node (ref "J2") (pin "1.1") (pinfunction "1_1.1") (pintype "passive"))
      (node (ref "L3") (pin "2") (pinfunction "2_2") (pintype "passive"))
      (node (ref "R41") (pin "1") (pinfunction "1_1") (pintype "passive"))
      (node (ref "ZD3") (pin "C") (pinfunction "C_C") (pintype "passive"))
    )
    (net (code "167") (name "VOUT_LC2+") (class "Default")
      (node (ref "C76") (pin "2") (pinfunction "2_2") (pintype "passive"))
      (node (ref "C77") (pin "1") (pinfunction "1_1") (pintype "passive"))
      (node (ref "C81") (pin "1") (pinfunction "+_1") (pintype "passive"))
      (node (ref "CH2") (pin "TIP") (pinfunction "TIP_TIP") (pintype "bidirectional"))
      (node (ref "J4") (pin "1") (pinfunction "1_1") (pintype "passive"))
      (node (ref "J4") (pin "1.1") (pinfunction "1_1.1") (pintype "passive"))
      (node (ref "L5") (pin "2") (pinfunction "2_2") (pintype "passive"))
      (node (ref "R65") (pin "1") (pinfunction "1_1") (pintype "passive"))
      (node (ref "ZD5") (pin "C") (pinfunction "C_C") (pintype "passive"))
    )
    (net (code "168") (name "VREF1") (class "Default")
      (node (ref "C53") (pin "1") (pinfunction "1_1") (pintype "passive"))
      (node (ref "IC11") (pin "10") (pinfunction "FBIN_10") (pintype "input"))
      (node (ref "IC11") (pin "13") (pinfunction "CTRL2_13") (pintype "input"))
      (node (ref "IC11") (pin "5") (pinfunction "VREF_5") (pintype "output"))
      (node (ref "R50") (pin "2") (pinfunction "2_2") (pintype "passive"))
    )
    (net (code "169") (name "VREF2") (class "Default")
      (node (ref "C73") (pin "1") (pinfunction "1_1") (pintype "passive"))
      (node (ref "IC13") (pin "10") (pinfunction "FBIN_10") (pintype "input"))
      (node (ref "IC13") (pin "13") (pinfunction "CTRL2_13") (pintype "input"))
      (node (ref "IC13") (pin "5") (pinfunction "VREF_5") (pintype "output"))
      (node (ref "R74") (pin "2") (pinfunction "2_2") (pintype "passive"))
    )
    (net (code "170") (name "unconnected-(IC8-PA2-Pad12)") (class "Default")
      (node (ref "IC8") (pin "12") (pinfunction "PA2_12") (pintype "bidirectional"))
    )
    (net (code "171") (name "unconnected-(IC8-PA3-Pad13)") (class "Default")
      (node (ref "IC8") (pin "13") (pinfunction "PA3_13") (pintype "bidirectional"))
    )
    (net (code "172") (name "unconnected-(IC8-PA8-Pad29)") (class "Default")
      (node (ref "IC8") (pin "29") (pinfunction "PA8_29") (pintype "bidirectional"))
    )
    (net (code "173") (name "unconnected-(IC8-PA15-Pad38)") (class "Default")
      (node (ref "IC8") (pin "38") (pinfunction "PA15_38") (pintype "bidirectional"))
    )
    (net (code "174") (name "unconnected-(IC8-PB7-Pad43)") (class "Default")
      (node (ref "IC8") (pin "43") (pinfunction "PB7_43") (pintype "bidirectional"))
    )
    (net (code "175") (name "unconnected-(IC8-PE9-Pad22)") (class "Default")
      (node (ref "IC8") (pin "22") (pinfunction "PE9_22") (pintype "bidirectional"))
    )
    (net (code "176") (name "unconnected-(IC8-PF6-Pad35)") (class "Default")
      (node (ref "IC8") (pin "35") (pinfunction "PF6_35") (pintype "bidirectional"))
    )
    (net (code "177") (name "unconnected-(IC8-VBAT-Pad1)") (class "Default")
      (node (ref "IC8") (pin "1") (pinfunction "VBAT_1") (pintype "passive"))
    )
    (net (code "178") (name "unconnected-(IC11-IVINMON-Pad8)") (class "Default")
      (node (ref "IC11") (pin "8") (pinfunction "IVINMON_8") (pintype "output"))
    )
    (net (code "179") (name "unconnected-(IC11-PWMOUT-Pad24)") (class "Default")
      (node (ref "IC11") (pin "24") (pinfunction "PWMOUT_24") (pintype "output"))
    )
    (net (code "180") (name "unconnected-(IC13-IVINMON-Pad8)") (class "Default")
      (node (ref "IC13") (pin "8") (pinfunction "IVINMON_8") (pintype "output"))
    )
    (net (code "181") (name "unconnected-(IC13-PWMOUT-Pad24)") (class "Default")
      (node (ref "IC13") (pin "24") (pinfunction "PWMOUT_24") (pintype "output"))
    )
    (net (code "182") (name "~{RESET}") (class "Default")
      (node (ref "IC1") (pin "15") (pinfunction "B1_15") (pintype "output"))
      (node (ref "JP3") (pin "1") (pinfunction "1_1") (pintype "passive"))
    )
  )
)
